# CRBN-60.net
KiCad netlist of a schematic drawn in EAGLE
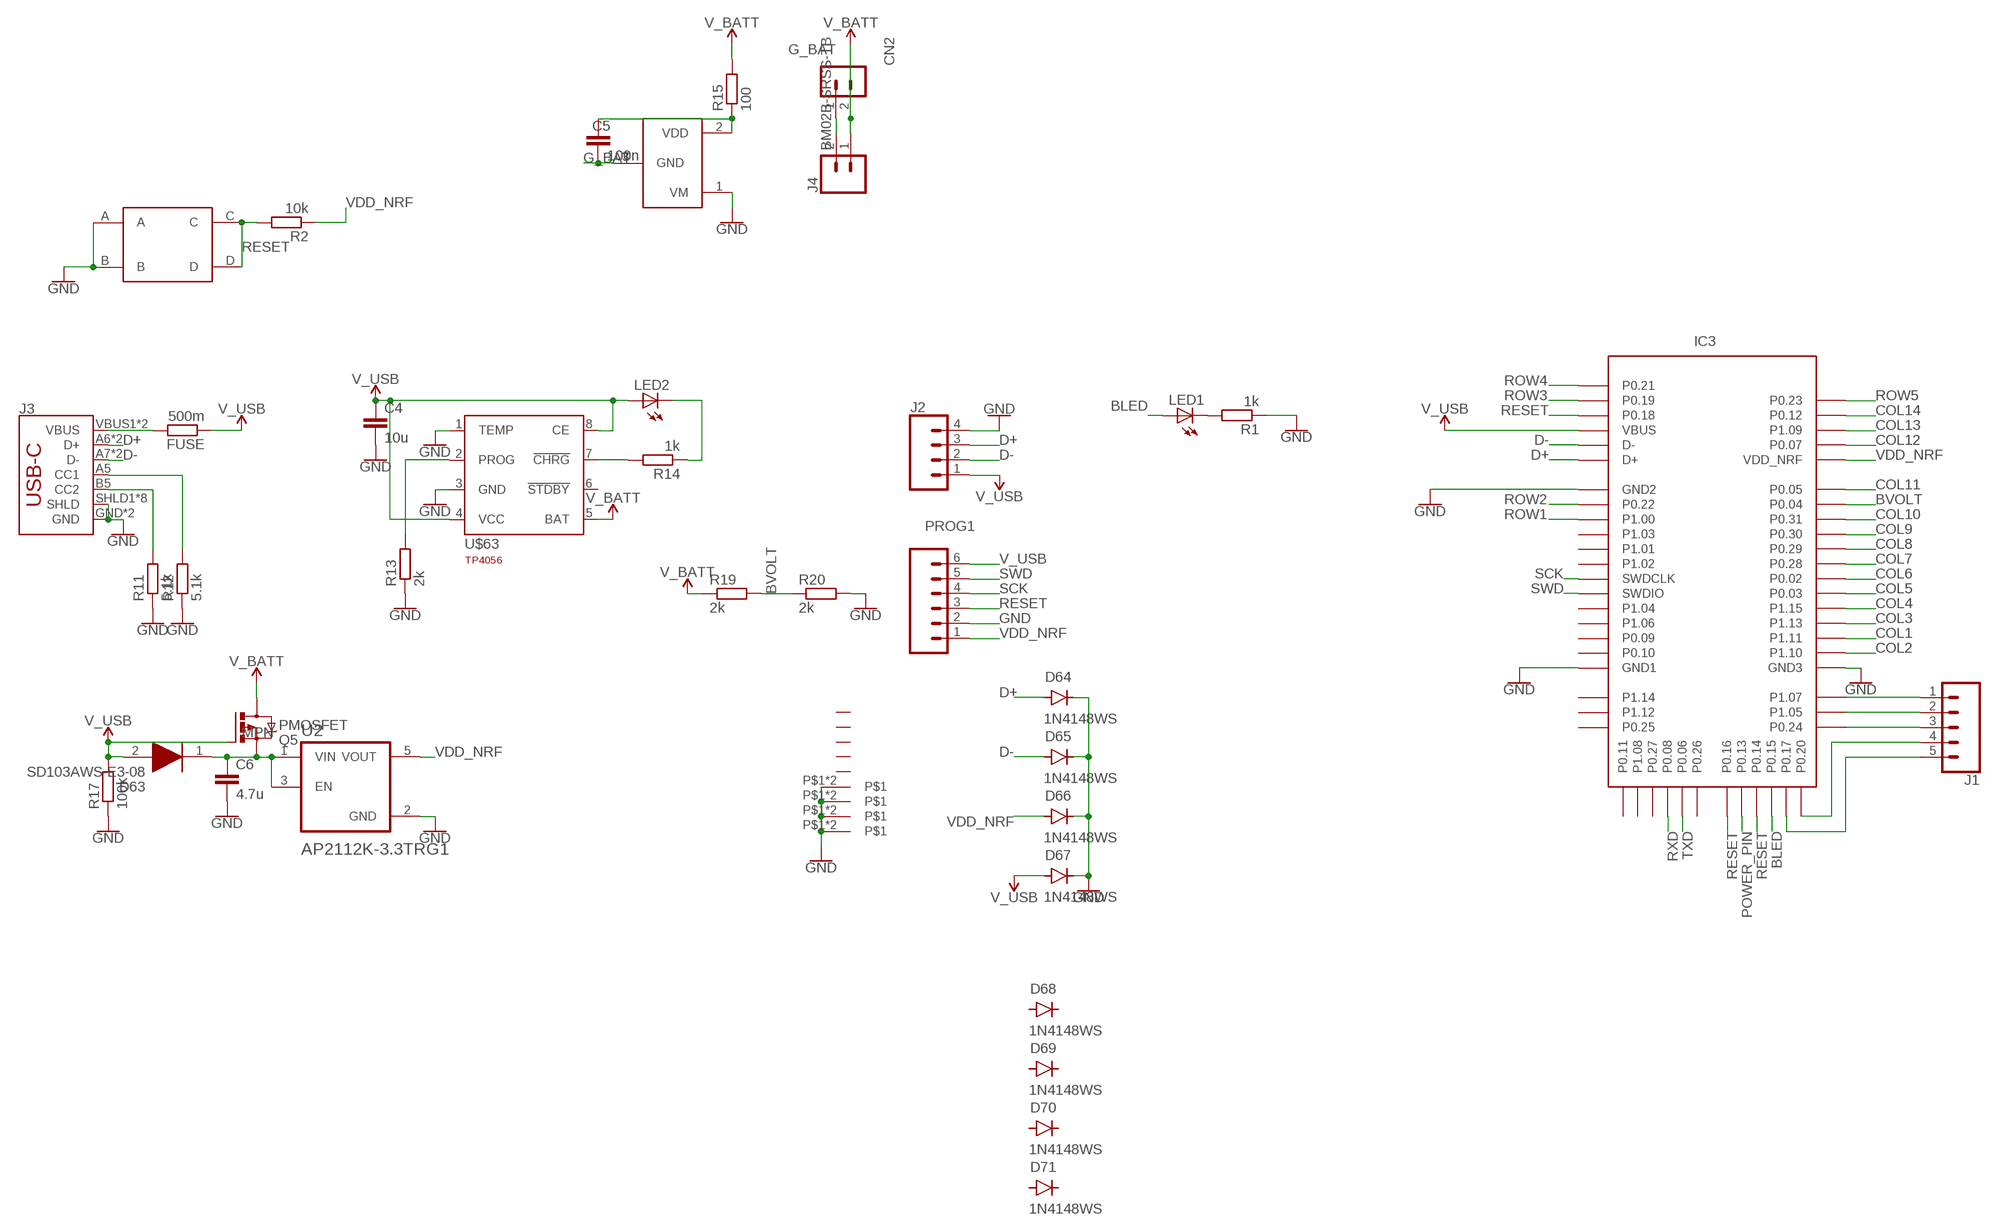
[diagram p0: schematic, sheet 1, part 1 of 2]
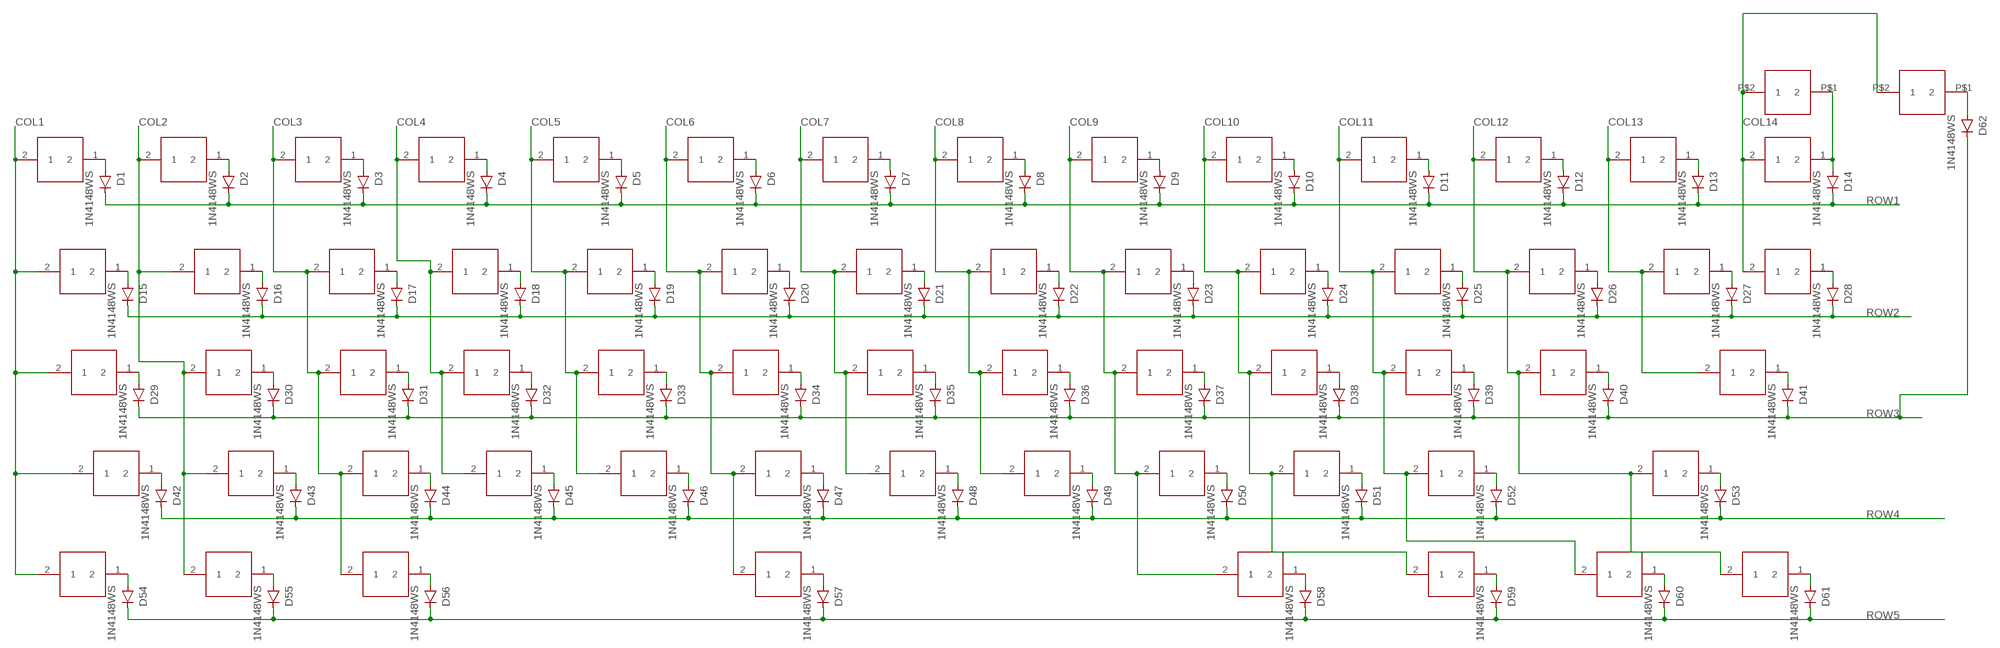
[diagram p1: schematic, sheet 1, part 2 of 2]

(export (version "E")
  (design (tool "Eeschema 10.0.6"))
  (components
    (comp (ref "C4")
      (value "10u")
      (footprint "eagle-import:C0603")
      (libsource (lib "eagle-import") (part "C-EUC0603"))
    )
    (comp (ref "C5")
      (value "100n")
      (footprint "eagle-import:C0603")
      (libsource (lib "eagle-import") (part "C-EUC0603"))
    )
    (comp (ref "C6")
      (value "4.7u")
      (footprint "eagle-import:C0603")
      (libsource (lib "eagle-import") (part "C-EUC0603"))
    )
    (comp (ref "CN2")
      (value "BM02B-SRSS-TB")
      (footprint "eagle-import:BM02B-SRSS-TB")
      (libsource (lib "eagle-import") (part "BM02B-SRSS-TB"))
    )
    (comp (ref "D1")
      (value "1N4148WS")
      (footprint "eagle-import:SOD-323")
      (fields
        (field (name "DIGIKEY_PART_NUMBER") "1N4148WSFSTR-ND")
        (field (name "MANUFACTURER") "Diodes Incorporated")
        (field (name "CREATED_BY") "PCBLayout.com")
      )
      (libsource (lib "eagle-import") (part "1N4148WS"))
    )
    (comp (ref "D2")
      (value "1N4148WS")
      (footprint "eagle-import:SOD-323")
      (fields
        (field (name "DIGIKEY_PART_NUMBER") "1N4148WSFSTR-ND")
        (field (name "MANUFACTURER") "Diodes Incorporated")
        (field (name "CREATED_BY") "PCBLayout.com")
      )
      (libsource (lib "eagle-import") (part "1N4148WS"))
    )
    (comp (ref "D3")
      (value "1N4148WS")
      (footprint "eagle-import:SOD-323")
      (fields
        (field (name "DIGIKEY_PART_NUMBER") "1N4148WSFSTR-ND")
        (field (name "MANUFACTURER") "Diodes Incorporated")
        (field (name "CREATED_BY") "PCBLayout.com")
      )
      (libsource (lib "eagle-import") (part "1N4148WS"))
    )
    (comp (ref "D4")
      (value "1N4148WS")
      (footprint "eagle-import:SOD-323")
      (fields
        (field (name "DIGIKEY_PART_NUMBER") "1N4148WSFSTR-ND")
        (field (name "MANUFACTURER") "Diodes Incorporated")
        (field (name "CREATED_BY") "PCBLayout.com")
      )
      (libsource (lib "eagle-import") (part "1N4148WS"))
    )
    (comp (ref "D5")
      (value "1N4148WS")
      (footprint "eagle-import:SOD-323")
      (fields
        (field (name "DIGIKEY_PART_NUMBER") "1N4148WSFSTR-ND")
        (field (name "MANUFACTURER") "Diodes Incorporated")
        (field (name "CREATED_BY") "PCBLayout.com")
      )
      (libsource (lib "eagle-import") (part "1N4148WS"))
    )
    (comp (ref "D6")
      (value "1N4148WS")
      (footprint "eagle-import:SOD-323")
      (fields
        (field (name "DIGIKEY_PART_NUMBER") "1N4148WSFSTR-ND")
        (field (name "MANUFACTURER") "Diodes Incorporated")
        (field (name "CREATED_BY") "PCBLayout.com")
      )
      (libsource (lib "eagle-import") (part "1N4148WS"))
    )
    (comp (ref "D7")
      (value "1N4148WS")
      (footprint "eagle-import:SOD-323")
      (fields
        (field (name "DIGIKEY_PART_NUMBER") "1N4148WSFSTR-ND")
        (field (name "MANUFACTURER") "Diodes Incorporated")
        (field (name "CREATED_BY") "PCBLayout.com")
      )
      (libsource (lib "eagle-import") (part "1N4148WS"))
    )
    (comp (ref "D8")
      (value "1N4148WS")
      (footprint "eagle-import:SOD-323")
      (fields
        (field (name "DIGIKEY_PART_NUMBER") "1N4148WSFSTR-ND")
        (field (name "MANUFACTURER") "Diodes Incorporated")
        (field (name "CREATED_BY") "PCBLayout.com")
      )
      (libsource (lib "eagle-import") (part "1N4148WS"))
    )
    (comp (ref "D9")
      (value "1N4148WS")
      (footprint "eagle-import:SOD-323")
      (fields
        (field (name "DIGIKEY_PART_NUMBER") "1N4148WSFSTR-ND")
        (field (name "MANUFACTURER") "Diodes Incorporated")
        (field (name "CREATED_BY") "PCBLayout.com")
      )
      (libsource (lib "eagle-import") (part "1N4148WS"))
    )
    (comp (ref "D10")
      (value "1N4148WS")
      (footprint "eagle-import:SOD-323")
      (fields
        (field (name "DIGIKEY_PART_NUMBER") "1N4148WSFSTR-ND")
        (field (name "MANUFACTURER") "Diodes Incorporated")
        (field (name "CREATED_BY") "PCBLayout.com")
      )
      (libsource (lib "eagle-import") (part "1N4148WS"))
    )
    (comp (ref "D11")
      (value "1N4148WS")
      (footprint "eagle-import:SOD-323")
      (fields
        (field (name "DIGIKEY_PART_NUMBER") "1N4148WSFSTR-ND")
        (field (name "MANUFACTURER") "Diodes Incorporated")
        (field (name "CREATED_BY") "PCBLayout.com")
      )
      (libsource (lib "eagle-import") (part "1N4148WS"))
    )
    (comp (ref "D12")
      (value "1N4148WS")
      (footprint "eagle-import:SOD-323")
      (fields
        (field (name "DIGIKEY_PART_NUMBER") "1N4148WSFSTR-ND")
        (field (name "MANUFACTURER") "Diodes Incorporated")
        (field (name "CREATED_BY") "PCBLayout.com")
      )
      (libsource (lib "eagle-import") (part "1N4148WS"))
    )
    (comp (ref "D13")
      (value "1N4148WS")
      (footprint "eagle-import:SOD-323")
      (fields
        (field (name "DIGIKEY_PART_NUMBER") "1N4148WSFSTR-ND")
        (field (name "MANUFACTURER") "Diodes Incorporated")
        (field (name "CREATED_BY") "PCBLayout.com")
      )
      (libsource (lib "eagle-import") (part "1N4148WS"))
    )
    (comp (ref "D14")
      (value "1N4148WS")
      (footprint "eagle-import:SOD-323")
      (fields
        (field (name "DIGIKEY_PART_NUMBER") "1N4148WSFSTR-ND")
        (field (name "MANUFACTURER") "Diodes Incorporated")
        (field (name "CREATED_BY") "PCBLayout.com")
      )
      (libsource (lib "eagle-import") (part "1N4148WS"))
    )
    (comp (ref "D15")
      (value "1N4148WS")
      (footprint "eagle-import:SOD-323")
      (fields
        (field (name "DIGIKEY_PART_NUMBER") "1N4148WSFSTR-ND")
        (field (name "MANUFACTURER") "Diodes Incorporated")
        (field (name "CREATED_BY") "PCBLayout.com")
      )
      (libsource (lib "eagle-import") (part "1N4148WS"))
    )
    (comp (ref "D16")
      (value "1N4148WS")
      (footprint "eagle-import:SOD-323")
      (fields
        (field (name "DIGIKEY_PART_NUMBER") "1N4148WSFSTR-ND")
        (field (name "MANUFACTURER") "Diodes Incorporated")
        (field (name "CREATED_BY") "PCBLayout.com")
      )
      (libsource (lib "eagle-import") (part "1N4148WS"))
    )
    (comp (ref "D17")
      (value "1N4148WS")
      (footprint "eagle-import:SOD-323")
      (fields
        (field (name "DIGIKEY_PART_NUMBER") "1N4148WSFSTR-ND")
        (field (name "MANUFACTURER") "Diodes Incorporated")
        (field (name "CREATED_BY") "PCBLayout.com")
      )
      (libsource (lib "eagle-import") (part "1N4148WS"))
    )
    (comp (ref "D18")
      (value "1N4148WS")
      (footprint "eagle-import:SOD-323")
      (fields
        (field (name "DIGIKEY_PART_NUMBER") "1N4148WSFSTR-ND")
        (field (name "MANUFACTURER") "Diodes Incorporated")
        (field (name "CREATED_BY") "PCBLayout.com")
      )
      (libsource (lib "eagle-import") (part "1N4148WS"))
    )
    (comp (ref "D19")
      (value "1N4148WS")
      (footprint "eagle-import:SOD-323")
      (fields
        (field (name "DIGIKEY_PART_NUMBER") "1N4148WSFSTR-ND")
        (field (name "MANUFACTURER") "Diodes Incorporated")
        (field (name "CREATED_BY") "PCBLayout.com")
      )
      (libsource (lib "eagle-import") (part "1N4148WS"))
    )
    (comp (ref "D20")
      (value "1N4148WS")
      (footprint "eagle-import:SOD-323")
      (fields
        (field (name "DIGIKEY_PART_NUMBER") "1N4148WSFSTR-ND")
        (field (name "MANUFACTURER") "Diodes Incorporated")
        (field (name "CREATED_BY") "PCBLayout.com")
      )
      (libsource (lib "eagle-import") (part "1N4148WS"))
    )
    (comp (ref "D21")
      (value "1N4148WS")
      (footprint "eagle-import:SOD-323")
      (fields
        (field (name "DIGIKEY_PART_NUMBER") "1N4148WSFSTR-ND")
        (field (name "MANUFACTURER") "Diodes Incorporated")
        (field (name "CREATED_BY") "PCBLayout.com")
      )
      (libsource (lib "eagle-import") (part "1N4148WS"))
    )
    (comp (ref "D22")
      (value "1N4148WS")
      (footprint "eagle-import:SOD-323")
      (fields
        (field (name "DIGIKEY_PART_NUMBER") "1N4148WSFSTR-ND")
        (field (name "MANUFACTURER") "Diodes Incorporated")
        (field (name "CREATED_BY") "PCBLayout.com")
      )
      (libsource (lib "eagle-import") (part "1N4148WS"))
    )
    (comp (ref "D23")
      (value "1N4148WS")
      (footprint "eagle-import:SOD-323")
      (fields
        (field (name "DIGIKEY_PART_NUMBER") "1N4148WSFSTR-ND")
        (field (name "MANUFACTURER") "Diodes Incorporated")
        (field (name "CREATED_BY") "PCBLayout.com")
      )
      (libsource (lib "eagle-import") (part "1N4148WS"))
    )
    (comp (ref "D24")
      (value "1N4148WS")
      (footprint "eagle-import:SOD-323")
      (fields
        (field (name "DIGIKEY_PART_NUMBER") "1N4148WSFSTR-ND")
        (field (name "MANUFACTURER") "Diodes Incorporated")
        (field (name "CREATED_BY") "PCBLayout.com")
      )
      (libsource (lib "eagle-import") (part "1N4148WS"))
    )
    (comp (ref "D25")
      (value "1N4148WS")
      (footprint "eagle-import:SOD-323")
      (fields
        (field (name "DIGIKEY_PART_NUMBER") "1N4148WSFSTR-ND")
        (field (name "MANUFACTURER") "Diodes Incorporated")
        (field (name "CREATED_BY") "PCBLayout.com")
      )
      (libsource (lib "eagle-import") (part "1N4148WS"))
    )
    (comp (ref "D26")
      (value "1N4148WS")
      (footprint "eagle-import:SOD-323")
      (fields
        (field (name "DIGIKEY_PART_NUMBER") "1N4148WSFSTR-ND")
        (field (name "MANUFACTURER") "Diodes Incorporated")
        (field (name "CREATED_BY") "PCBLayout.com")
      )
      (libsource (lib "eagle-import") (part "1N4148WS"))
    )
    (comp (ref "D27")
      (value "1N4148WS")
      (footprint "eagle-import:SOD-323")
      (fields
        (field (name "DIGIKEY_PART_NUMBER") "1N4148WSFSTR-ND")
        (field (name "MANUFACTURER") "Diodes Incorporated")
        (field (name "CREATED_BY") "PCBLayout.com")
      )
      (libsource (lib "eagle-import") (part "1N4148WS"))
    )
    (comp (ref "D28")
      (value "1N4148WS")
      (footprint "eagle-import:SOD-323")
      (fields
        (field (name "DIGIKEY_PART_NUMBER") "1N4148WSFSTR-ND")
        (field (name "MANUFACTURER") "Diodes Incorporated")
        (field (name "CREATED_BY") "PCBLayout.com")
      )
      (libsource (lib "eagle-import") (part "1N4148WS"))
    )
    (comp (ref "D29")
      (value "1N4148WS")
      (footprint "eagle-import:SOD-323")
      (fields
        (field (name "DIGIKEY_PART_NUMBER") "1N4148WSFSTR-ND")
        (field (name "MANUFACTURER") "Diodes Incorporated")
        (field (name "CREATED_BY") "PCBLayout.com")
      )
      (libsource (lib "eagle-import") (part "1N4148WS"))
    )
    (comp (ref "D30")
      (value "1N4148WS")
      (footprint "eagle-import:SOD-323")
      (fields
        (field (name "DIGIKEY_PART_NUMBER") "1N4148WSFSTR-ND")
        (field (name "MANUFACTURER") "Diodes Incorporated")
        (field (name "CREATED_BY") "PCBLayout.com")
      )
      (libsource (lib "eagle-import") (part "1N4148WS"))
    )
    (comp (ref "D31")
      (value "1N4148WS")
      (footprint "eagle-import:SOD-323")
      (fields
        (field (name "DIGIKEY_PART_NUMBER") "1N4148WSFSTR-ND")
        (field (name "MANUFACTURER") "Diodes Incorporated")
        (field (name "CREATED_BY") "PCBLayout.com")
      )
      (libsource (lib "eagle-import") (part "1N4148WS"))
    )
    (comp (ref "D32")
      (value "1N4148WS")
      (footprint "eagle-import:SOD-323")
      (fields
        (field (name "DIGIKEY_PART_NUMBER") "1N4148WSFSTR-ND")
        (field (name "MANUFACTURER") "Diodes Incorporated")
        (field (name "CREATED_BY") "PCBLayout.com")
      )
      (libsource (lib "eagle-import") (part "1N4148WS"))
    )
    (comp (ref "D33")
      (value "1N4148WS")
      (footprint "eagle-import:SOD-323")
      (fields
        (field (name "DIGIKEY_PART_NUMBER") "1N4148WSFSTR-ND")
        (field (name "MANUFACTURER") "Diodes Incorporated")
        (field (name "CREATED_BY") "PCBLayout.com")
      )
      (libsource (lib "eagle-import") (part "1N4148WS"))
    )
    (comp (ref "D34")
      (value "1N4148WS")
      (footprint "eagle-import:SOD-323")
      (fields
        (field (name "DIGIKEY_PART_NUMBER") "1N4148WSFSTR-ND")
        (field (name "MANUFACTURER") "Diodes Incorporated")
        (field (name "CREATED_BY") "PCBLayout.com")
      )
      (libsource (lib "eagle-import") (part "1N4148WS"))
    )
    (comp (ref "D35")
      (value "1N4148WS")
      (footprint "eagle-import:SOD-323")
      (fields
        (field (name "DIGIKEY_PART_NUMBER") "1N4148WSFSTR-ND")
        (field (name "MANUFACTURER") "Diodes Incorporated")
        (field (name "CREATED_BY") "PCBLayout.com")
      )
      (libsource (lib "eagle-import") (part "1N4148WS"))
    )
    (comp (ref "D36")
      (value "1N4148WS")
      (footprint "eagle-import:SOD-323")
      (fields
        (field (name "DIGIKEY_PART_NUMBER") "1N4148WSFSTR-ND")
        (field (name "MANUFACTURER") "Diodes Incorporated")
        (field (name "CREATED_BY") "PCBLayout.com")
      )
      (libsource (lib "eagle-import") (part "1N4148WS"))
    )
    (comp (ref "D37")
      (value "1N4148WS")
      (footprint "eagle-import:SOD-323")
      (fields
        (field (name "DIGIKEY_PART_NUMBER") "1N4148WSFSTR-ND")
        (field (name "MANUFACTURER") "Diodes Incorporated")
        (field (name "CREATED_BY") "PCBLayout.com")
      )
      (libsource (lib "eagle-import") (part "1N4148WS"))
    )
    (comp (ref "D38")
      (value "1N4148WS")
      (footprint "eagle-import:SOD-323")
      (fields
        (field (name "DIGIKEY_PART_NUMBER") "1N4148WSFSTR-ND")
        (field (name "MANUFACTURER") "Diodes Incorporated")
        (field (name "CREATED_BY") "PCBLayout.com")
      )
      (libsource (lib "eagle-import") (part "1N4148WS"))
    )
    (comp (ref "D39")
      (value "1N4148WS")
      (footprint "eagle-import:SOD-323")
      (fields
        (field (name "DIGIKEY_PART_NUMBER") "1N4148WSFSTR-ND")
        (field (name "MANUFACTURER") "Diodes Incorporated")
        (field (name "CREATED_BY") "PCBLayout.com")
      )
      (libsource (lib "eagle-import") (part "1N4148WS"))
    )
    (comp (ref "D40")
      (value "1N4148WS")
      (footprint "eagle-import:SOD-323")
      (fields
        (field (name "DIGIKEY_PART_NUMBER") "1N4148WSFSTR-ND")
        (field (name "MANUFACTURER") "Diodes Incorporated")
        (field (name "CREATED_BY") "PCBLayout.com")
      )
      (libsource (lib "eagle-import") (part "1N4148WS"))
    )
    (comp (ref "D41")
      (value "1N4148WS")
      (footprint "eagle-import:SOD-323")
      (fields
        (field (name "DIGIKEY_PART_NUMBER") "1N4148WSFSTR-ND")
        (field (name "MANUFACTURER") "Diodes Incorporated")
        (field (name "CREATED_BY") "PCBLayout.com")
      )
      (libsource (lib "eagle-import") (part "1N4148WS"))
    )
    (comp (ref "D42")
      (value "1N4148WS")
      (footprint "eagle-import:SOD-323")
      (fields
        (field (name "DIGIKEY_PART_NUMBER") "1N4148WSFSTR-ND")
        (field (name "MANUFACTURER") "Diodes Incorporated")
        (field (name "CREATED_BY") "PCBLayout.com")
      )
      (libsource (lib "eagle-import") (part "1N4148WS"))
    )
    (comp (ref "D43")
      (value "1N4148WS")
      (footprint "eagle-import:SOD-323")
      (fields
        (field (name "DIGIKEY_PART_NUMBER") "1N4148WSFSTR-ND")
        (field (name "MANUFACTURER") "Diodes Incorporated")
        (field (name "CREATED_BY") "PCBLayout.com")
      )
      (libsource (lib "eagle-import") (part "1N4148WS"))
    )
    (comp (ref "D44")
      (value "1N4148WS")
      (footprint "eagle-import:SOD-323")
      (fields
        (field (name "DIGIKEY_PART_NUMBER") "1N4148WSFSTR-ND")
        (field (name "MANUFACTURER") "Diodes Incorporated")
        (field (name "CREATED_BY") "PCBLayout.com")
      )
      (libsource (lib "eagle-import") (part "1N4148WS"))
    )
    (comp (ref "D45")
      (value "1N4148WS")
      (footprint "eagle-import:SOD-323")
      (fields
        (field (name "DIGIKEY_PART_NUMBER") "1N4148WSFSTR-ND")
        (field (name "MANUFACTURER") "Diodes Incorporated")
        (field (name "CREATED_BY") "PCBLayout.com")
      )
      (libsource (lib "eagle-import") (part "1N4148WS"))
    )
    (comp (ref "D46")
      (value "1N4148WS")
      (footprint "eagle-import:SOD-323")
      (fields
        (field (name "DIGIKEY_PART_NUMBER") "1N4148WSFSTR-ND")
        (field (name "MANUFACTURER") "Diodes Incorporated")
        (field (name "CREATED_BY") "PCBLayout.com")
      )
      (libsource (lib "eagle-import") (part "1N4148WS"))
    )
    (comp (ref "D47")
      (value "1N4148WS")
      (footprint "eagle-import:SOD-323")
      (fields
        (field (name "DIGIKEY_PART_NUMBER") "1N4148WSFSTR-ND")
        (field (name "MANUFACTURER") "Diodes Incorporated")
        (field (name "CREATED_BY") "PCBLayout.com")
      )
      (libsource (lib "eagle-import") (part "1N4148WS"))
    )
    (comp (ref "D48")
      (value "1N4148WS")
      (footprint "eagle-import:SOD-323")
      (fields
        (field (name "DIGIKEY_PART_NUMBER") "1N4148WSFSTR-ND")
        (field (name "MANUFACTURER") "Diodes Incorporated")
        (field (name "CREATED_BY") "PCBLayout.com")
      )
      (libsource (lib "eagle-import") (part "1N4148WS"))
    )
    (comp (ref "D49")
      (value "1N4148WS")
      (footprint "eagle-import:SOD-323")
      (fields
        (field (name "DIGIKEY_PART_NUMBER") "1N4148WSFSTR-ND")
        (field (name "MANUFACTURER") "Diodes Incorporated")
        (field (name "CREATED_BY") "PCBLayout.com")
      )
      (libsource (lib "eagle-import") (part "1N4148WS"))
    )
    (comp (ref "D50")
      (value "1N4148WS")
      (footprint "eagle-import:SOD-323")
      (fields
        (field (name "DIGIKEY_PART_NUMBER") "1N4148WSFSTR-ND")
        (field (name "MANUFACTURER") "Diodes Incorporated")
        (field (name "CREATED_BY") "PCBLayout.com")
      )
      (libsource (lib "eagle-import") (part "1N4148WS"))
    )
    (comp (ref "D51")
      (value "1N4148WS")
      (footprint "eagle-import:SOD-323")
      (fields
        (field (name "DIGIKEY_PART_NUMBER") "1N4148WSFSTR-ND")
        (field (name "MANUFACTURER") "Diodes Incorporated")
        (field (name "CREATED_BY") "PCBLayout.com")
      )
      (libsource (lib "eagle-import") (part "1N4148WS"))
    )
    (comp (ref "D52")
      (value "1N4148WS")
      (footprint "eagle-import:SOD-323")
      (fields
        (field (name "DIGIKEY_PART_NUMBER") "1N4148WSFSTR-ND")
        (field (name "MANUFACTURER") "Diodes Incorporated")
        (field (name "CREATED_BY") "PCBLayout.com")
      )
      (libsource (lib "eagle-import") (part "1N4148WS"))
    )
    (comp (ref "D53")
      (value "1N4148WS")
      (footprint "eagle-import:SOD-323")
      (fields
        (field (name "DIGIKEY_PART_NUMBER") "1N4148WSFSTR-ND")
        (field (name "MANUFACTURER") "Diodes Incorporated")
        (field (name "CREATED_BY") "PCBLayout.com")
      )
      (libsource (lib "eagle-import") (part "1N4148WS"))
    )
    (comp (ref "D54")
      (value "1N4148WS")
      (footprint "eagle-import:SOD-323")
      (fields
        (field (name "DIGIKEY_PART_NUMBER") "1N4148WSFSTR-ND")
        (field (name "MANUFACTURER") "Diodes Incorporated")
        (field (name "CREATED_BY") "PCBLayout.com")
      )
      (libsource (lib "eagle-import") (part "1N4148WS"))
    )
    (comp (ref "D55")
      (value "1N4148WS")
      (footprint "eagle-import:SOD-323")
      (fields
        (field (name "DIGIKEY_PART_NUMBER") "1N4148WSFSTR-ND")
        (field (name "MANUFACTURER") "Diodes Incorporated")
        (field (name "CREATED_BY") "PCBLayout.com")
      )
      (libsource (lib "eagle-import") (part "1N4148WS"))
    )
    (comp (ref "D56")
      (value "1N4148WS")
      (footprint "eagle-import:SOD-323")
      (fields
        (field (name "DIGIKEY_PART_NUMBER") "1N4148WSFSTR-ND")
        (field (name "MANUFACTURER") "Diodes Incorporated")
        (field (name "CREATED_BY") "PCBLayout.com")
      )
      (libsource (lib "eagle-import") (part "1N4148WS"))
    )
    (comp (ref "D57")
      (value "1N4148WS")
      (footprint "eagle-import:SOD-323")
      (fields
        (field (name "DIGIKEY_PART_NUMBER") "1N4148WSFSTR-ND")
        (field (name "MANUFACTURER") "Diodes Incorporated")
        (field (name "CREATED_BY") "PCBLayout.com")
      )
      (libsource (lib "eagle-import") (part "1N4148WS"))
    )
    (comp (ref "D58")
      (value "1N4148WS")
      (footprint "eagle-import:SOD-323")
      (fields
        (field (name "DIGIKEY_PART_NUMBER") "1N4148WSFSTR-ND")
        (field (name "MANUFACTURER") "Diodes Incorporated")
        (field (name "CREATED_BY") "PCBLayout.com")
      )
      (libsource (lib "eagle-import") (part "1N4148WS"))
    )
    (comp (ref "D59")
      (value "1N4148WS")
      (footprint "eagle-import:SOD-323")
      (fields
        (field (name "DIGIKEY_PART_NUMBER") "1N4148WSFSTR-ND")
        (field (name "MANUFACTURER") "Diodes Incorporated")
        (field (name "CREATED_BY") "PCBLayout.com")
      )
      (libsource (lib "eagle-import") (part "1N4148WS"))
    )
    (comp (ref "D60")
      (value "1N4148WS")
      (footprint "eagle-import:SOD-323")
      (fields
        (field (name "DIGIKEY_PART_NUMBER") "1N4148WSFSTR-ND")
        (field (name "MANUFACTURER") "Diodes Incorporated")
        (field (name "CREATED_BY") "PCBLayout.com")
      )
      (libsource (lib "eagle-import") (part "1N4148WS"))
    )
    (comp (ref "D61")
      (value "1N4148WS")
      (footprint "eagle-import:SOD-323")
      (fields
        (field (name "DIGIKEY_PART_NUMBER") "1N4148WSFSTR-ND")
        (field (name "MANUFACTURER") "Diodes Incorporated")
        (field (name "CREATED_BY") "PCBLayout.com")
      )
      (libsource (lib "eagle-import") (part "1N4148WS"))
    )
    (comp (ref "D62")
      (value "1N4148WS")
      (footprint "eagle-import:SOD-323")
      (fields
        (field (name "DIGIKEY_PART_NUMBER") "1N4148WSFSTR-ND")
        (field (name "MANUFACTURER") "Diodes Incorporated")
        (field (name "CREATED_BY") "PCBLayout.com")
      )
      (libsource (lib "eagle-import") (part "1N4148WS"))
    )
    (comp (ref "D63")
      (value "SD103AWS-E3-08")
      (footprint "eagle-import:SOD2713X115N")
      (fields (field (name "MOUSER_PART_NUMBER") "78-SD103AWS-E3-08"))
      (libsource (lib "eagle-import") (part "SD103AWS-E3-08"))
    )
    (comp (ref "D64")
      (value "1N4148WS")
      (footprint "eagle-import:SOD-323")
      (fields
        (field (name "DIGIKEY_PART_NUMBER") "1N4148WSFSTR-ND")
        (field (name "MANUFACTURER") "Diodes Incorporated")
        (field (name "CREATED_BY") "PCBLayout.com")
      )
      (libsource (lib "eagle-import") (part "1N4148WS"))
    )
    (comp (ref "D65")
      (value "1N4148WS")
      (footprint "eagle-import:SOD-323")
      (fields
        (field (name "DIGIKEY_PART_NUMBER") "1N4148WSFSTR-ND")
        (field (name "MANUFACTURER") "Diodes Incorporated")
        (field (name "CREATED_BY") "PCBLayout.com")
      )
      (libsource (lib "eagle-import") (part "1N4148WS"))
    )
    (comp (ref "D66")
      (value "1N4148WS")
      (footprint "eagle-import:SOD-323")
      (fields
        (field (name "DIGIKEY_PART_NUMBER") "1N4148WSFSTR-ND")
        (field (name "MANUFACTURER") "Diodes Incorporated")
        (field (name "CREATED_BY") "PCBLayout.com")
      )
      (libsource (lib "eagle-import") (part "1N4148WS"))
    )
    (comp (ref "D67")
      (value "1N4148WS")
      (footprint "eagle-import:SOD-323")
      (fields
        (field (name "DIGIKEY_PART_NUMBER") "1N4148WSFSTR-ND")
        (field (name "MANUFACTURER") "Diodes Incorporated")
        (field (name "CREATED_BY") "PCBLayout.com")
      )
      (libsource (lib "eagle-import") (part "1N4148WS"))
    )
    (comp (ref "D68")
      (value "1N4148WS")
      (footprint "eagle-import:SOD-323")
      (fields
        (field (name "DIGIKEY_PART_NUMBER") "1N4148WSFSTR-ND")
        (field (name "MANUFACTURER") "Diodes Incorporated")
        (field (name "CREATED_BY") "PCBLayout.com")
      )
      (libsource (lib "eagle-import") (part "1N4148WS"))
    )
    (comp (ref "D69")
      (value "1N4148WS")
      (footprint "eagle-import:SOD-323")
      (fields
        (field (name "DIGIKEY_PART_NUMBER") "1N4148WSFSTR-ND")
        (field (name "MANUFACTURER") "Diodes Incorporated")
        (field (name "CREATED_BY") "PCBLayout.com")
      )
      (libsource (lib "eagle-import") (part "1N4148WS"))
    )
    (comp (ref "D70")
      (value "1N4148WS")
      (footprint "eagle-import:SOD-323")
      (fields
        (field (name "DIGIKEY_PART_NUMBER") "1N4148WSFSTR-ND")
        (field (name "MANUFACTURER") "Diodes Incorporated")
        (field (name "CREATED_BY") "PCBLayout.com")
      )
      (libsource (lib "eagle-import") (part "1N4148WS"))
    )
    (comp (ref "D71")
      (value "1N4148WS")
      (footprint "eagle-import:SOD-323")
      (fields
        (field (name "DIGIKEY_PART_NUMBER") "1N4148WSFSTR-ND")
        (field (name "MANUFACTURER") "Diodes Incorporated")
        (field (name "CREATED_BY") "PCBLayout.com")
      )
      (libsource (lib "eagle-import") (part "1N4148WS"))
    )
    (comp (ref "FUSE")
      (value "500m")
      (footprint "eagle-import:R0603")
      (libsource (lib "eagle-import") (part "R-EU_R0603"))
    )
    (comp (ref "IC1")
      (value "XB3303ASOT23")
      (footprint "eagle-import:SOT23-3")
      (libsource (lib "eagle-import") (part "XB3303ASOT23"))
    )
    (comp (ref "IC3")
      (value "HOLYIOT_18010")
      (footprint "eagle-import:PCBCOMPONENT_1")
      (libsource (lib "eagle-import") (part "HOLYIOT_18010"))
    )
    (comp (ref "J1")
      (value "CONN_051.27MM")
      (footprint "eagle-import:1X05_1.27MM")
      (libsource (lib "eagle-import") (part "CONN_051.27MM"))
    )
    (comp (ref "J2")
      (value "CONN_041X04_NO_SILK")
      (footprint "eagle-import:1X04_NO_SILK")
      (libsource (lib "eagle-import") (part "CONN_041X04_NO_SILK"))
    )
    (comp (ref "J3")
      (value "SPARKFUN-CONNECTORS_USB_C16PIN")
      (footprint "eagle-import:SPARKFUN-CONNECTORS_USB-C-16P")
      (libsource (lib "eagle-import") (part "SPARKFUN-CONNECTORS_USB_C16PIN"))
    )
    (comp (ref "J4")
      (value "CONN_02")
      (footprint "eagle-import:1X02")
      (libsource (lib "eagle-import") (part "CONN_02"))
    )
    (comp (ref "LED1")
      (value "LEDCHIPLED_0805")
      (footprint "eagle-import:CHIPLED_0805")
      (libsource (lib "eagle-import") (part "LEDCHIPLED_0805"))
    )
    (comp (ref "LED2")
      (value "LEDCHIPLED_0805")
      (footprint "eagle-import:CHIPLED_0805")
      (libsource (lib "eagle-import") (part "LEDCHIPLED_0805"))
    )
    (comp (ref "PROG1")
      (value "CONN_06NO_SILK_FEMALE_PTH")
      (footprint "eagle-import:1X06_NO_SILK")
      (libsource (lib "eagle-import") (part "CONN_06NO_SILK_FEMALE_PTH"))
    )
    (comp (ref "Q5")
      (value "PMOSFET")
      (footprint "eagle-import:SOT23")
      (fields (field (name "MPN") "SL2301S"))
      (libsource (lib "eagle-import") (part "PMOSFETSOT23_"))
    )
    (comp (ref "R1")
      (value "1k")
      (footprint "eagle-import:R0603")
      (libsource (lib "eagle-import") (part "R-EU_R0603"))
    )
    (comp (ref "R2")
      (value "10k")
      (footprint "eagle-import:R0603")
      (libsource (lib "eagle-import") (part "R-EU_R0603"))
    )
    (comp (ref "R11")
      (value "5.1k")
      (footprint "eagle-import:R0603")
      (libsource (lib "eagle-import") (part "R-EU_R0603"))
    )
    (comp (ref "R12")
      (value "5.1k")
      (footprint "eagle-import:R0603")
      (libsource (lib "eagle-import") (part "R-EU_R0603"))
    )
    (comp (ref "R13")
      (value "2k")
      (footprint "eagle-import:R0603")
      (libsource (lib "eagle-import") (part "R-EU_R0603"))
    )
    (comp (ref "R14")
      (value "1k")
      (footprint "eagle-import:R0603")
      (libsource (lib "eagle-import") (part "R-EU_R0603"))
    )
    (comp (ref "R15")
      (value "100")
      (footprint "eagle-import:R0603")
      (libsource (lib "eagle-import") (part "R-EU_R0603"))
    )
    (comp (ref "R17")
      (value "100k")
      (footprint "eagle-import:R0603")
      (libsource (lib "eagle-import") (part "R-EU_R0603"))
    )
    (comp (ref "R19")
      (value "2k")
      (footprint "eagle-import:R0603")
      (libsource (lib "eagle-import") (part "R-EU_R0603"))
    )
    (comp (ref "R20")
      (value "2k")
      (footprint "eagle-import:R0603")
      (libsource (lib "eagle-import") (part "R-EU_R0603"))
    )
    (comp (ref "U$1")
      (value "CHERRY")
      (footprint "eagle-import:CHERRY")
      (libsource (lib "eagle-import") (part "CHERRY"))
    )
    (comp (ref "U$2")
      (value "CHERRY")
      (footprint "eagle-import:CHERRY")
      (libsource (lib "eagle-import") (part "CHERRY"))
    )
    (comp (ref "U$3")
      (value "CHERRY")
      (footprint "eagle-import:CHERRY")
      (libsource (lib "eagle-import") (part "CHERRY"))
    )
    (comp (ref "U$4")
      (value "CHERRY")
      (footprint "eagle-import:CHERRY")
      (libsource (lib "eagle-import") (part "CHERRY"))
    )
    (comp (ref "U$5")
      (value "CHERRY")
      (footprint "eagle-import:CHERRY")
      (libsource (lib "eagle-import") (part "CHERRY"))
    )
    (comp (ref "U$6")
      (value "CHERRY")
      (footprint "eagle-import:CHERRY")
      (libsource (lib "eagle-import") (part "CHERRY"))
    )
    (comp (ref "U$7")
      (value "CHERRY")
      (footprint "eagle-import:CHERRY")
      (libsource (lib "eagle-import") (part "CHERRY"))
    )
    (comp (ref "U$8")
      (value "CHERRY")
      (footprint "eagle-import:CHERRY")
      (libsource (lib "eagle-import") (part "CHERRY"))
    )
    (comp (ref "U$9")
      (value "CHERRY")
      (footprint "eagle-import:CHERRY")
      (libsource (lib "eagle-import") (part "CHERRY"))
    )
    (comp (ref "U$10")
      (value "CHERRY")
      (footprint "eagle-import:CHERRY")
      (libsource (lib "eagle-import") (part "CHERRY"))
    )
    (comp (ref "U$11")
      (value "CHERRY")
      (footprint "eagle-import:CHERRY")
      (libsource (lib "eagle-import") (part "CHERRY"))
    )
    (comp (ref "U$12")
      (value "CHERRY")
      (footprint "eagle-import:CHERRY")
      (libsource (lib "eagle-import") (part "CHERRY"))
    )
    (comp (ref "U$13")
      (value "CHERRY")
      (footprint "eagle-import:CHERRY")
      (libsource (lib "eagle-import") (part "CHERRY"))
    )
    (comp (ref "U$14")
      (value "CHERRY_CORNER_OFFED")
      (footprint "eagle-import:CHERRY_CORNER_OFFED")
      (libsource (lib "eagle-import") (part "CHERRY_CORNER_OFFED"))
    )
    (comp (ref "U$15")
      (value "CHERRY")
      (footprint "eagle-import:CHERRY")
      (libsource (lib "eagle-import") (part "CHERRY"))
    )
    (comp (ref "U$16")
      (value "CHERRY")
      (footprint "eagle-import:CHERRY")
      (libsource (lib "eagle-import") (part "CHERRY"))
    )
    (comp (ref "U$17")
      (value "CHERRY")
      (footprint "eagle-import:CHERRY")
      (libsource (lib "eagle-import") (part "CHERRY"))
    )
    (comp (ref "U$18")
      (value "CHERRY")
      (footprint "eagle-import:CHERRY")
      (libsource (lib "eagle-import") (part "CHERRY"))
    )
    (comp (ref "U$19")
      (value "CHERRY")
      (footprint "eagle-import:CHERRY")
      (libsource (lib "eagle-import") (part "CHERRY"))
    )
    (comp (ref "U$20")
      (value "CHERRY")
      (footprint "eagle-import:CHERRY")
      (libsource (lib "eagle-import") (part "CHERRY"))
    )
    (comp (ref "U$21")
      (value "CHERRY")
      (footprint "eagle-import:CHERRY")
      (libsource (lib "eagle-import") (part "CHERRY"))
    )
    (comp (ref "U$22")
      (value "CHERRY")
      (footprint "eagle-import:CHERRY")
      (libsource (lib "eagle-import") (part "CHERRY"))
    )
    (comp (ref "U$23")
      (value "CHERRY")
      (footprint "eagle-import:CHERRY")
      (libsource (lib "eagle-import") (part "CHERRY"))
    )
    (comp (ref "U$24")
      (value "CHERRY")
      (footprint "eagle-import:CHERRY")
      (libsource (lib "eagle-import") (part "CHERRY"))
    )
    (comp (ref "U$25")
      (value "CHERRY")
      (footprint "eagle-import:CHERRY")
      (libsource (lib "eagle-import") (part "CHERRY"))
    )
    (comp (ref "U$26")
      (value "CHERRY")
      (footprint "eagle-import:CHERRY")
      (libsource (lib "eagle-import") (part "CHERRY"))
    )
    (comp (ref "U$27")
      (value "CHERRY")
      (footprint "eagle-import:CHERRY")
      (libsource (lib "eagle-import") (part "CHERRY"))
    )
    (comp (ref "U$28")
      (value "CHERRY_CORNER_OFFED")
      (footprint "eagle-import:CHERRY_CORNER_OFFED")
      (libsource (lib "eagle-import") (part "CHERRY_CORNER_OFFED"))
    )
    (comp (ref "U$29")
      (value "CHERRY")
      (footprint "eagle-import:CHERRY")
      (libsource (lib "eagle-import") (part "CHERRY"))
    )
    (comp (ref "U$30")
      (value "CHERRY")
      (footprint "eagle-import:CHERRY")
      (libsource (lib "eagle-import") (part "CHERRY"))
    )
    (comp (ref "U$31")
      (value "CHERRY")
      (footprint "eagle-import:CHERRY")
      (libsource (lib "eagle-import") (part "CHERRY"))
    )
    (comp (ref "U$32")
      (value "CHERRY")
      (footprint "eagle-import:CHERRY")
      (libsource (lib "eagle-import") (part "CHERRY"))
    )
    (comp (ref "U$33")
      (value "CHERRY")
      (footprint "eagle-import:CHERRY")
      (libsource (lib "eagle-import") (part "CHERRY"))
    )
    (comp (ref "U$34")
      (value "CHERRY")
      (footprint "eagle-import:CHERRY")
      (libsource (lib "eagle-import") (part "CHERRY"))
    )
    (comp (ref "U$35")
      (value "CHERRY_CORNER_OFFED")
      (footprint "eagle-import:CHERRY_CORNER_OFFED")
      (libsource (lib "eagle-import") (part "CHERRY_CORNER_OFFED"))
    )
    (comp (ref "U$36")
      (value "CHERRY")
      (footprint "eagle-import:CHERRY")
      (libsource (lib "eagle-import") (part "CHERRY"))
    )
    (comp (ref "U$37")
      (value "CHERRY")
      (footprint "eagle-import:CHERRY")
      (libsource (lib "eagle-import") (part "CHERRY"))
    )
    (comp (ref "U$38")
      (value "CHERRY")
      (footprint "eagle-import:CHERRY")
      (libsource (lib "eagle-import") (part "CHERRY"))
    )
    (comp (ref "U$39")
      (value "CHERRY")
      (footprint "eagle-import:CHERRY")
      (libsource (lib "eagle-import") (part "CHERRY"))
    )
    (comp (ref "U$40")
      (value "CHERRY")
      (footprint "eagle-import:CHERRY")
      (libsource (lib "eagle-import") (part "CHERRY"))
    )
    (comp (ref "U$41")
      (value "CHERRY")
      (footprint "eagle-import:CHERRY")
      (libsource (lib "eagle-import") (part "CHERRY"))
    )
    (comp (ref "U$42")
      (value "CHERRY")
      (footprint "eagle-import:CHERRY")
      (libsource (lib "eagle-import") (part "CHERRY"))
    )
    (comp (ref "U$43")
      (value "CHERRY")
      (footprint "eagle-import:CHERRY")
      (libsource (lib "eagle-import") (part "CHERRY"))
    )
    (comp (ref "U$44")
      (value "CHERRY")
      (footprint "eagle-import:CHERRY")
      (libsource (lib "eagle-import") (part "CHERRY"))
    )
    (comp (ref "U$45")
      (value "CHERRY")
      (footprint "eagle-import:CHERRY")
      (libsource (lib "eagle-import") (part "CHERRY"))
    )
    (comp (ref "U$46")
      (value "CHERRY")
      (footprint "eagle-import:CHERRY")
      (libsource (lib "eagle-import") (part "CHERRY"))
    )
    (comp (ref "U$47")
      (value "CHERRY")
      (footprint "eagle-import:CHERRY")
      (libsource (lib "eagle-import") (part "CHERRY"))
    )
    (comp (ref "U$48")
      (value "CHERRY")
      (footprint "eagle-import:CHERRY")
      (libsource (lib "eagle-import") (part "CHERRY"))
    )
    (comp (ref "U$49")
      (value "CHERRY")
      (footprint "eagle-import:CHERRY")
      (libsource (lib "eagle-import") (part "CHERRY"))
    )
    (comp (ref "U$50")
      (value "CHERRY")
      (footprint "eagle-import:CHERRY")
      (libsource (lib "eagle-import") (part "CHERRY"))
    )
    (comp (ref "U$51")
      (value "CHERRY")
      (footprint "eagle-import:CHERRY")
      (libsource (lib "eagle-import") (part "CHERRY"))
    )
    (comp (ref "U$52")
      (value "CHERRY")
      (footprint "eagle-import:CHERRY")
      (libsource (lib "eagle-import") (part "CHERRY"))
    )
    (comp (ref "U$53")
      (value "CHERRY")
      (footprint "eagle-import:CHERRY")
      (libsource (lib "eagle-import") (part "CHERRY"))
    )
    (comp (ref "U$54")
      (value "CHERRY")
      (footprint "eagle-import:CHERRY")
      (libsource (lib "eagle-import") (part "CHERRY"))
    )
    (comp (ref "U$55")
      (value "CHERRY")
      (footprint "eagle-import:CHERRY")
      (libsource (lib "eagle-import") (part "CHERRY"))
    )
    (comp (ref "U$56")
      (value "CHERRY")
      (footprint "eagle-import:CHERRY")
      (libsource (lib "eagle-import") (part "CHERRY"))
    )
    (comp (ref "U$57")
      (value "CHERRY")
      (footprint "eagle-import:CHERRY")
      (libsource (lib "eagle-import") (part "CHERRY"))
    )
    (comp (ref "U$58")
      (value "CHERRY")
      (footprint "eagle-import:CHERRY")
      (libsource (lib "eagle-import") (part "CHERRY"))
    )
    (comp (ref "U$59")
      (value "CHERRY")
      (footprint "eagle-import:CHERRY")
      (libsource (lib "eagle-import") (part "CHERRY"))
    )
    (comp (ref "U$60")
      (value "CHERRY")
      (footprint "eagle-import:CHERRY")
      (libsource (lib "eagle-import") (part "CHERRY"))
    )
    (comp (ref "U$61")
      (value "CHERRY")
      (footprint "eagle-import:CHERRY")
      (libsource (lib "eagle-import") (part "CHERRY"))
    )
    (comp (ref "U$62")
      (value "SMD-BUTTON")
      (footprint "eagle-import:SMD-BUTTON")
      (libsource (lib "eagle-import") (part "SMD-BUTTON"))
    )
    (comp (ref "U$63")
      (value "TP4056SOI8")
      (footprint "eagle-import:SOIC8")
      (libsource (lib "eagle-import") (part "TP4056SOI8"))
    )
    (comp (ref "U$64")
      (value "2.5MM_ELONGATED")
      (footprint "eagle-import:2.5MM_ELONGATED")
      (libsource (lib "eagle-import") (part "2.5MM_ELONGATED"))
    )
    (comp (ref "U$65")
      (value "2.5MM_ELONGATED")
      (footprint "eagle-import:2.5MM_ELONGATED")
      (libsource (lib "eagle-import") (part "2.5MM_ELONGATED"))
    )
    (comp (ref "U$66")
      (value "2.5MM_HOLE")
      (footprint "eagle-import:2.5MM_HOLE")
      (libsource (lib "eagle-import") (part "2.5MM_HOLE"))
    )
    (comp (ref "U$67")
      (value "2.5MM_ELONGATED")
      (footprint "eagle-import:2.5MM_ELONGATED")
      (libsource (lib "eagle-import") (part "2.5MM_ELONGATED"))
    )
    (comp (ref "U$68")
      (value "STAB-2U")
      (footprint "eagle-import:STAB-2U")
      (libsource (lib "eagle-import") (part "STAB-2U"))
    )
    (comp (ref "U$69")
      (value "STAB-2U")
      (footprint "eagle-import:STAB-2U")
      (libsource (lib "eagle-import") (part "STAB-2U"))
    )
    (comp (ref "U$70")
      (value "STAB-2U")
      (footprint "eagle-import:STAB-2U")
      (libsource (lib "eagle-import") (part "STAB-2U"))
    )
    (comp (ref "U$71")
      (value "STAB-2U")
      (footprint "eagle-import:STAB-2U")
      (libsource (lib "eagle-import") (part "STAB-2U"))
    )
    (comp (ref "U$72")
      (value "STAB-6U")
      (footprint "eagle-import:STAB-6.25U")
      (libsource (lib "eagle-import") (part "STAB-6U"))
    )
    (comp (ref "U$73")
      (value "CHERRY-SOLDER")
      (footprint "eagle-import:CHERRY-SOLDER")
      (libsource (lib "eagle-import") (part "CHERRY-SOLDER"))
    )
    (comp (ref "U$74")
      (value "CHERRY-SOLDER")
      (footprint "eagle-import:CHERRY-SOLDER")
      (libsource (lib "eagle-import") (part "CHERRY-SOLDER"))
    )
    (comp (ref "U2")
      (value "AP2112K-3.3TRG1")
      (footprint "eagle-import:SOT95P285X140-5N")
      (fields (field (name "MF") "Diodes Inc."))
      (libsource (lib "eagle-import") (part "AP2112K-3.3TRG1"))
    )
  )
  (nets
    (net (code "1") (name "/BLED") (class "Default")
      (node (ref "IC3") (pin "P0.15") (pinfunction "P0.15_P0.15") (pintype "bidirectional"))
      (node (ref "LED1") (pin "A") (pinfunction "A_A") (pintype "passive"))
    )
    (net (code "2") (name "/BVOLT") (class "Default")
      (node (ref "IC3") (pin "P0.04") (pinfunction "P0.04_P0.04") (pintype "bidirectional"))
      (node (ref "R19") (pin "2") (pinfunction "2_2") (pintype "passive"))
      (node (ref "R20") (pin "1") (pinfunction "1_1") (pintype "passive"))
    )
    (net (code "3") (name "/COL1") (class "Default")
      (node (ref "IC3") (pin "P1.11") (pinfunction "P1.11_P1.11") (pintype "bidirectional"))
      (node (ref "U$1") (pin "2") (pinfunction "1_2") (pintype "bidirectional"))
      (node (ref "U$15") (pin "2") (pinfunction "1_2") (pintype "bidirectional"))
      (node (ref "U$29") (pin "2") (pinfunction "1_2") (pintype "bidirectional"))
      (node (ref "U$42") (pin "2") (pinfunction "1_2") (pintype "bidirectional"))
      (node (ref "U$54") (pin "2") (pinfunction "1_2") (pintype "bidirectional"))
    )
    (net (code "4") (name "/COL2") (class "Default")
      (node (ref "IC3") (pin "P1.10") (pinfunction "P1.10_P1.10") (pintype "bidirectional"))
      (node (ref "U$16") (pin "2") (pinfunction "1_2") (pintype "bidirectional"))
      (node (ref "U$2") (pin "2") (pinfunction "1_2") (pintype "bidirectional"))
      (node (ref "U$30") (pin "2") (pinfunction "1_2") (pintype "bidirectional"))
      (node (ref "U$43") (pin "2") (pinfunction "1_2") (pintype "bidirectional"))
      (node (ref "U$55") (pin "2") (pinfunction "1_2") (pintype "bidirectional"))
    )
    (net (code "5") (name "/COL3") (class "Default")
      (node (ref "IC3") (pin "P1.13") (pinfunction "P1.13_P1.13") (pintype "bidirectional"))
      (node (ref "U$17") (pin "2") (pinfunction "1_2") (pintype "bidirectional"))
      (node (ref "U$3") (pin "2") (pinfunction "1_2") (pintype "bidirectional"))
      (node (ref "U$31") (pin "2") (pinfunction "1_2") (pintype "bidirectional"))
      (node (ref "U$44") (pin "2") (pinfunction "1_2") (pintype "bidirectional"))
      (node (ref "U$56") (pin "2") (pinfunction "1_2") (pintype "bidirectional"))
    )
    (net (code "6") (name "/COL4") (class "Default")
      (node (ref "IC3") (pin "P1.15") (pinfunction "P1.15_P1.15") (pintype "bidirectional"))
      (node (ref "U$18") (pin "2") (pinfunction "1_2") (pintype "bidirectional"))
      (node (ref "U$32") (pin "2") (pinfunction "1_2") (pintype "bidirectional"))
      (node (ref "U$4") (pin "2") (pinfunction "1_2") (pintype "bidirectional"))
      (node (ref "U$45") (pin "2") (pinfunction "1_2") (pintype "bidirectional"))
    )
    (net (code "7") (name "/COL5") (class "Default")
      (node (ref "IC3") (pin "P0.03") (pinfunction "P0.03_P0.03") (pintype "bidirectional"))
      (node (ref "U$19") (pin "2") (pinfunction "1_2") (pintype "bidirectional"))
      (node (ref "U$33") (pin "2") (pinfunction "1_2") (pintype "bidirectional"))
      (node (ref "U$46") (pin "2") (pinfunction "1_2") (pintype "bidirectional"))
      (node (ref "U$5") (pin "2") (pinfunction "1_2") (pintype "bidirectional"))
    )
    (net (code "8") (name "/COL6") (class "Default")
      (node (ref "IC3") (pin "P0.02") (pinfunction "P0.02_P0.02") (pintype "bidirectional"))
      (node (ref "U$20") (pin "2") (pinfunction "1_2") (pintype "bidirectional"))
      (node (ref "U$34") (pin "2") (pinfunction "1_2") (pintype "bidirectional"))
      (node (ref "U$47") (pin "2") (pinfunction "1_2") (pintype "bidirectional"))
      (node (ref "U$57") (pin "2") (pinfunction "1_2") (pintype "bidirectional"))
      (node (ref "U$6") (pin "2") (pinfunction "1_2") (pintype "bidirectional"))
    )
    (net (code "9") (name "/COL7") (class "Default")
      (node (ref "IC3") (pin "P0.28") (pinfunction "P0.28_P0.28") (pintype "bidirectional"))
      (node (ref "U$21") (pin "2") (pinfunction "1_2") (pintype "bidirectional"))
      (node (ref "U$35") (pin "2") (pinfunction "1_2") (pintype "bidirectional"))
      (node (ref "U$48") (pin "2") (pinfunction "1_2") (pintype "bidirectional"))
      (node (ref "U$7") (pin "2") (pinfunction "1_2") (pintype "bidirectional"))
    )
    (net (code "10") (name "/COL8") (class "Default")
      (node (ref "IC3") (pin "P0.29") (pinfunction "P0.29_P0.29") (pintype "bidirectional"))
      (node (ref "U$22") (pin "2") (pinfunction "1_2") (pintype "bidirectional"))
      (node (ref "U$36") (pin "2") (pinfunction "1_2") (pintype "bidirectional"))
      (node (ref "U$49") (pin "2") (pinfunction "1_2") (pintype "bidirectional"))
      (node (ref "U$8") (pin "2") (pinfunction "1_2") (pintype "bidirectional"))
    )
    (net (code "11") (name "/COL9") (class "Default")
      (node (ref "IC3") (pin "P0.30") (pinfunction "P0.30_P0.30") (pintype "bidirectional"))
      (node (ref "U$23") (pin "2") (pinfunction "1_2") (pintype "bidirectional"))
      (node (ref "U$37") (pin "2") (pinfunction "1_2") (pintype "bidirectional"))
      (node (ref "U$50") (pin "2") (pinfunction "1_2") (pintype "bidirectional"))
      (node (ref "U$58") (pin "2") (pinfunction "1_2") (pintype "bidirectional"))
      (node (ref "U$9") (pin "2") (pinfunction "1_2") (pintype "bidirectional"))
    )
    (net (code "12") (name "/COL10") (class "Default")
      (node (ref "IC3") (pin "P0.31") (pinfunction "P0.31_P0.31") (pintype "bidirectional"))
      (node (ref "U$10") (pin "2") (pinfunction "1_2") (pintype "bidirectional"))
      (node (ref "U$24") (pin "2") (pinfunction "1_2") (pintype "bidirectional"))
      (node (ref "U$38") (pin "2") (pinfunction "1_2") (pintype "bidirectional"))
      (node (ref "U$51") (pin "2") (pinfunction "1_2") (pintype "bidirectional"))
      (node (ref "U$59") (pin "2") (pinfunction "1_2") (pintype "bidirectional"))
    )
    (net (code "13") (name "/COL11") (class "Default")
      (node (ref "IC3") (pin "P0.05") (pinfunction "P0.05_P0.05") (pintype "bidirectional"))
      (node (ref "U$11") (pin "2") (pinfunction "1_2") (pintype "bidirectional"))
      (node (ref "U$25") (pin "2") (pinfunction "1_2") (pintype "bidirectional"))
      (node (ref "U$39") (pin "2") (pinfunction "1_2") (pintype "bidirectional"))
      (node (ref "U$52") (pin "2") (pinfunction "1_2") (pintype "bidirectional"))
      (node (ref "U$60") (pin "2") (pinfunction "1_2") (pintype "bidirectional"))
    )
    (net (code "14") (name "/COL12") (class "Default")
      (node (ref "IC3") (pin "P0.07") (pinfunction "P0.07_P0.07") (pintype "bidirectional"))
      (node (ref "U$12") (pin "2") (pinfunction "1_2") (pintype "bidirectional"))
      (node (ref "U$26") (pin "2") (pinfunction "1_2") (pintype "bidirectional"))
      (node (ref "U$40") (pin "2") (pinfunction "1_2") (pintype "bidirectional"))
      (node (ref "U$53") (pin "2") (pinfunction "1_2") (pintype "bidirectional"))
      (node (ref "U$61") (pin "2") (pinfunction "1_2") (pintype "bidirectional"))
    )
    (net (code "15") (name "/COL13") (class "Default")
      (node (ref "IC3") (pin "P1.09") (pinfunction "P1.09_P1.09") (pintype "bidirectional"))
      (node (ref "U$13") (pin "2") (pinfunction "1_2") (pintype "bidirectional"))
      (node (ref "U$27") (pin "2") (pinfunction "1_2") (pintype "bidirectional"))
      (node (ref "U$41") (pin "2") (pinfunction "1_2") (pintype "bidirectional"))
    )
    (net (code "16") (name "/COL14") (class "Default")
      (node (ref "IC3") (pin "P0.12") (pinfunction "P0.12_P0.12") (pintype "bidirectional"))
      (node (ref "U$14") (pin "2") (pinfunction "1_2") (pintype "bidirectional"))
      (node (ref "U$28") (pin "2") (pinfunction "1_2") (pintype "bidirectional"))
      (node (ref "U$73") (pin "P$2") (pinfunction "1_P$2") (pintype "bidirectional"))
      (node (ref "U$74") (pin "P$2") (pinfunction "1_P$2") (pintype "bidirectional"))
    )
    (net (code "17") (name "/D+") (class "Default")
      (node (ref "D64") (pin "A") (pinfunction "A_A") (pintype "passive"))
      (node (ref "IC3") (pin "D+") (pinfunction "D+_D+") (pintype "bidirectional"))
      (node (ref "J2") (pin "3") (pinfunction "3_3") (pintype "passive"))
      (node (ref "J3") (pin "A6") (pinfunction "D+_A6") (pintype "bidirectional"))
      (node (ref "J3") (pin "B6") (pinfunction "D+_B6") (pintype "bidirectional"))
    )
    (net (code "18") (name "/D-") (class "Default")
      (node (ref "D65") (pin "A") (pinfunction "A_A") (pintype "passive"))
      (node (ref "IC3") (pin "D-") (pinfunction "D-_D-") (pintype "bidirectional"))
      (node (ref "J2") (pin "2") (pinfunction "2_2") (pintype "passive"))
      (node (ref "J3") (pin "A7") (pinfunction "D-_A7") (pintype "bidirectional"))
      (node (ref "J3") (pin "B7") (pinfunction "D-_B7") (pintype "bidirectional"))
    )
    (net (code "19") (name "/G_BAT") (class "Default")
      (node (ref "C5") (pin "2") (pinfunction "2_2") (pintype "passive"))
      (node (ref "CN2") (pin "1") (pinfunction "1_1") (pintype "passive"))
      (node (ref "IC1") (pin "3") (pinfunction "GND_3") (pintype "bidirectional"))
      (node (ref "J4") (pin "2") (pinfunction "2_2") (pintype "passive"))
    )
    (net (code "20") (name "/POWER_PIN") (class "Default")
      (node (ref "IC3") (pin "P0.13") (pinfunction "P0.13_P0.13") (pintype "bidirectional"))
    )
    (net (code "21") (name "/RESET") (class "Default")
      (node (ref "IC3") (pin "P0.14") (pinfunction "P0.14_P0.14") (pintype "bidirectional"))
      (node (ref "IC3") (pin "P0.16") (pinfunction "P0.16_P0.16") (pintype "bidirectional"))
      (node (ref "IC3") (pin "P0.18") (pinfunction "P0.18_P0.18") (pintype "bidirectional"))
      (node (ref "PROG1") (pin "3") (pinfunction "3_3") (pintype "passive"))
      (node (ref "R2") (pin "2") (pinfunction "2_2") (pintype "passive"))
      (node (ref "U$62") (pin "C") (pinfunction "C_C") (pintype "bidirectional"))
      (node (ref "U$62") (pin "D") (pinfunction "D_D") (pintype "bidirectional"))
    )
    (net (code "22") (name "/ROW1") (class "Default")
      (node (ref "D1") (pin "C") (pinfunction "C_C") (pintype "passive"))
      (node (ref "D10") (pin "C") (pinfunction "C_C") (pintype "passive"))
      (node (ref "D11") (pin "C") (pinfunction "C_C") (pintype "passive"))
      (node (ref "D12") (pin "C") (pinfunction "C_C") (pintype "passive"))
      (node (ref "D13") (pin "C") (pinfunction "C_C") (pintype "passive"))
      (node (ref "D14") (pin "C") (pinfunction "C_C") (pintype "passive"))
      (node (ref "D2") (pin "C") (pinfunction "C_C") (pintype "passive"))
      (node (ref "D3") (pin "C") (pinfunction "C_C") (pintype "passive"))
      (node (ref "D4") (pin "C") (pinfunction "C_C") (pintype "passive"))
      (node (ref "D5") (pin "C") (pinfunction "C_C") (pintype "passive"))
      (node (ref "D6") (pin "C") (pinfunction "C_C") (pintype "passive"))
      (node (ref "D7") (pin "C") (pinfunction "C_C") (pintype "passive"))
      (node (ref "D8") (pin "C") (pinfunction "C_C") (pintype "passive"))
      (node (ref "D9") (pin "C") (pinfunction "C_C") (pintype "passive"))
      (node (ref "IC3") (pin "P1.00") (pinfunction "P1.00_P1.00") (pintype "bidirectional"))
    )
    (net (code "23") (name "/ROW2") (class "Default")
      (node (ref "D15") (pin "C") (pinfunction "C_C") (pintype "passive"))
      (node (ref "D16") (pin "C") (pinfunction "C_C") (pintype "passive"))
      (node (ref "D17") (pin "C") (pinfunction "C_C") (pintype "passive"))
      (node (ref "D18") (pin "C") (pinfunction "C_C") (pintype "passive"))
      (node (ref "D19") (pin "C") (pinfunction "C_C") (pintype "passive"))
      (node (ref "D20") (pin "C") (pinfunction "C_C") (pintype "passive"))
      (node (ref "D21") (pin "C") (pinfunction "C_C") (pintype "passive"))
      (node (ref "D22") (pin "C") (pinfunction "C_C") (pintype "passive"))
      (node (ref "D23") (pin "C") (pinfunction "C_C") (pintype "passive"))
      (node (ref "D24") (pin "C") (pinfunction "C_C") (pintype "passive"))
      (node (ref "D25") (pin "C") (pinfunction "C_C") (pintype "passive"))
      (node (ref "D26") (pin "C") (pinfunction "C_C") (pintype "passive"))
      (node (ref "D27") (pin "C") (pinfunction "C_C") (pintype "passive"))
      (node (ref "D28") (pin "C") (pinfunction "C_C") (pintype "passive"))
      (node (ref "IC3") (pin "P0.22") (pinfunction "P0.22_P0.22") (pintype "bidirectional"))
    )
    (net (code "24") (name "/ROW3") (class "Default")
      (node (ref "D29") (pin "C") (pinfunction "C_C") (pintype "passive"))
      (node (ref "D30") (pin "C") (pinfunction "C_C") (pintype "passive"))
      (node (ref "D31") (pin "C") (pinfunction "C_C") (pintype "passive"))
      (node (ref "D32") (pin "C") (pinfunction "C_C") (pintype "passive"))
      (node (ref "D33") (pin "C") (pinfunction "C_C") (pintype "passive"))
      (node (ref "D34") (pin "C") (pinfunction "C_C") (pintype "passive"))
      (node (ref "D35") (pin "C") (pinfunction "C_C") (pintype "passive"))
      (node (ref "D36") (pin "C") (pinfunction "C_C") (pintype "passive"))
      (node (ref "D37") (pin "C") (pinfunction "C_C") (pintype "passive"))
      (node (ref "D38") (pin "C") (pinfunction "C_C") (pintype "passive"))
      (node (ref "D39") (pin "C") (pinfunction "C_C") (pintype "passive"))
      (node (ref "D40") (pin "C") (pinfunction "C_C") (pintype "passive"))
      (node (ref "D41") (pin "C") (pinfunction "C_C") (pintype "passive"))
      (node (ref "D62") (pin "C") (pinfunction "C_C") (pintype "passive"))
      (node (ref "IC3") (pin "P0.19") (pinfunction "P0.19_P0.19") (pintype "bidirectional"))
    )
    (net (code "25") (name "/ROW4") (class "Default")
      (node (ref "D42") (pin "C") (pinfunction "C_C") (pintype "passive"))
      (node (ref "D43") (pin "C") (pinfunction "C_C") (pintype "passive"))
      (node (ref "D44") (pin "C") (pinfunction "C_C") (pintype "passive"))
      (node (ref "D45") (pin "C") (pinfunction "C_C") (pintype "passive"))
      (node (ref "D46") (pin "C") (pinfunction "C_C") (pintype "passive"))
      (node (ref "D47") (pin "C") (pinfunction "C_C") (pintype "passive"))
      (node (ref "D48") (pin "C") (pinfunction "C_C") (pintype "passive"))
      (node (ref "D49") (pin "C") (pinfunction "C_C") (pintype "passive"))
      (node (ref "D50") (pin "C") (pinfunction "C_C") (pintype "passive"))
      (node (ref "D51") (pin "C") (pinfunction "C_C") (pintype "passive"))
      (node (ref "D52") (pin "C") (pinfunction "C_C") (pintype "passive"))
      (node (ref "D53") (pin "C") (pinfunction "C_C") (pintype "passive"))
      (node (ref "IC3") (pin "P0.21") (pinfunction "P0.21_P0.21") (pintype "bidirectional"))
    )
    (net (code "26") (name "/ROW5") (class "Default")
      (node (ref "D54") (pin "C") (pinfunction "C_C") (pintype "passive"))
      (node (ref "D55") (pin "C") (pinfunction "C_C") (pintype "passive"))
      (node (ref "D56") (pin "C") (pinfunction "C_C") (pintype "passive"))
      (node (ref "D57") (pin "C") (pinfunction "C_C") (pintype "passive"))
      (node (ref "D58") (pin "C") (pinfunction "C_C") (pintype "passive"))
      (node (ref "D59") (pin "C") (pinfunction "C_C") (pintype "passive"))
      (node (ref "D60") (pin "C") (pinfunction "C_C") (pintype "passive"))
      (node (ref "D61") (pin "C") (pinfunction "C_C") (pintype "passive"))
      (node (ref "IC3") (pin "P0.23") (pinfunction "P0.23_P0.23") (pintype "bidirectional"))
    )
    (net (code "27") (name "/RXD") (class "Default")
      (node (ref "IC3") (pin "P0.08") (pinfunction "P0.08_P0.08") (pintype "bidirectional"))
    )
    (net (code "28") (name "/SCK") (class "Default")
      (node (ref "IC3") (pin "SWDCLK") (pinfunction "SWDCLK_SWDCLK") (pintype "bidirectional"))
      (node (ref "PROG1") (pin "4") (pinfunction "4_4") (pintype "passive"))
    )
    (net (code "29") (name "/SWD") (class "Default")
      (node (ref "IC3") (pin "SWDIO") (pinfunction "SWDIO_SWDIO") (pintype "bidirectional"))
      (node (ref "PROG1") (pin "5") (pinfunction "5_5") (pintype "passive"))
    )
    (net (code "30") (name "/TXD") (class "Default")
      (node (ref "IC3") (pin "P0.06") (pinfunction "P0.06_P0.06") (pintype "bidirectional"))
    )
    (net (code "31") (name "/VDD_NRF") (class "Default")
      (node (ref "D66") (pin "A") (pinfunction "A_A") (pintype "passive"))
      (node (ref "IC3") (pin "VDD_NRF") (pinfunction "VDD_NRF_VDD_NRF") (pintype "bidirectional"))
      (node (ref "PROG1") (pin "1") (pinfunction "1_1") (pintype "passive"))
      (node (ref "R2") (pin "1") (pinfunction "1_1") (pintype "passive"))
      (node (ref "U2") (pin "5") (pinfunction "VOUT_5") (pintype "power_in"))
    )
    (net (code "32") (name "GND") (class "Default")
      (node (ref "C4") (pin "2") (pinfunction "2_2") (pintype "passive"))
      (node (ref "C6") (pin "2") (pinfunction "2_2") (pintype "passive"))
      (node (ref "D64") (pin "C") (pinfunction "C_C") (pintype "passive"))
      (node (ref "D65") (pin "C") (pinfunction "C_C") (pintype "passive"))
      (node (ref "D66") (pin "C") (pinfunction "C_C") (pintype "passive"))
      (node (ref "D67") (pin "C") (pinfunction "C_C") (pintype "passive"))
      (node (ref "IC1") (pin "1") (pinfunction "VM_1") (pintype "bidirectional"))
      (node (ref "IC3") (pin "GND") (pinfunction "GND1_GND") (pintype "bidirectional"))
      (node (ref "IC3") (pin "GND1") (pinfunction "GND2_GND1") (pintype "bidirectional"))
      (node (ref "IC3") (pin "GND2") (pinfunction "GND3_GND2") (pintype "bidirectional"))
      (node (ref "J2") (pin "4") (pinfunction "4_4") (pintype "passive"))
      (node (ref "J3") (pin "GND") (pinfunction "GND_GND") (pintype "bidirectional"))
      (node (ref "J3") (pin "GND2") (pinfunction "GND_GND2") (pintype "bidirectional"))
      (node (ref "J3") (pin "SHLD1") (pinfunction "SHLD_SHLD1") (pintype "bidirectional"))
      (node (ref "J3") (pin "SHLD2") (pinfunction "SHLD_SHLD2") (pintype "bidirectional"))
      (node (ref "J3") (pin "SHLD3") (pinfunction "SHLD_SHLD3") (pintype "bidirectional"))
      (node (ref "J3") (pin "SHLD4") (pinfunction "SHLD_SHLD4") (pintype "bidirectional"))
      (node (ref "J3") (pin "SHLD5") (pinfunction "SHLD_SHLD5") (pintype "bidirectional"))
      (node (ref "J3") (pin "SHLD6") (pinfunction "SHLD_SHLD6") (pintype "bidirectional"))
      (node (ref "J3") (pin "SHLD7") (pinfunction "SHLD_SHLD7") (pintype "bidirectional"))
      (node (ref "J3") (pin "SHLD8") (pinfunction "SHLD_SHLD8") (pintype "bidirectional"))
      (node (ref "PROG1") (pin "2") (pinfunction "2_2") (pintype "passive"))
      (node (ref "R1") (pin "1") (pinfunction "1_1") (pintype "passive"))
      (node (ref "R11") (pin "1") (pinfunction "1_1") (pintype "passive"))
      (node (ref "R12") (pin "1") (pinfunction "1_1") (pintype "passive"))
      (node (ref "R13") (pin "1") (pinfunction "1_1") (pintype "passive"))
      (node (ref "R17") (pin "1") (pinfunction "1_1") (pintype "passive"))
      (node (ref "R20") (pin "2") (pinfunction "2_2") (pintype "passive"))
      (node (ref "U$62") (pin "A") (pinfunction "A_A") (pintype "bidirectional"))
      (node (ref "U$62") (pin "B") (pinfunction "B_B") (pintype "bidirectional"))
      (node (ref "U$63") (pin "1") (pinfunction "TEMP_1") (pintype "bidirectional"))
      (node (ref "U$63") (pin "3") (pinfunction "GND_3") (pintype "bidirectional"))
      (node (ref "U$64") (pin "P$1") (pinfunction "P$1_P$1") (pintype "bidirectional"))
      (node (ref "U$64") (pin "P$2") (pinfunction "P$1_P$2") (pintype "bidirectional"))
      (node (ref "U$65") (pin "P$1") (pinfunction "P$1_P$1") (pintype "bidirectional"))
      (node (ref "U$65") (pin "P$2") (pinfunction "P$1_P$2") (pintype "bidirectional"))
      (node (ref "U$66") (pin "P$1") (pinfunction "P$1_P$1") (pintype "bidirectional"))
      (node (ref "U$66") (pin "P$2") (pinfunction "P$1_P$2") (pintype "bidirectional"))
      (node (ref "U$67") (pin "P$1") (pinfunction "P$1_P$1") (pintype "bidirectional"))
      (node (ref "U$67") (pin "P$2") (pinfunction "P$1_P$2") (pintype "bidirectional"))
      (node (ref "U2") (pin "2") (pinfunction "GND_2") (pintype "power_in"))
    )
    (net (code "33") (name "Net-(D63-K)") (class "Default")
      (node (ref "C6") (pin "1") (pinfunction "1_1") (pintype "passive"))
      (node (ref "D63") (pin "1") (pinfunction "K_1") (pintype "bidirectional"))
      (node (ref "Q5") (pin "2") (pinfunction "S_2") (pintype "passive"))
      (node (ref "U2") (pin "1") (pinfunction "VIN_1") (pintype "power_in"))
      (node (ref "U2") (pin "3") (pinfunction "EN_3") (pintype "input"))
    )
    (net (code "34") (name "Net-(FUSE-Pad2)") (class "Default")
      (node (ref "FUSE") (pin "2") (pinfunction "2_2") (pintype "passive"))
      (node (ref "J3") (pin "VBUS1") (pinfunction "VBUS_VBUS1") (pintype "bidirectional"))
      (node (ref "J3") (pin "VBUS2") (pinfunction "VBUS_VBUS2") (pintype "bidirectional"))
    )
    (net (code "35") (name "Net-(IC1-VDD)") (class "Default")
      (node (ref "C5") (pin "1") (pinfunction "1_1") (pintype "passive"))
      (node (ref "IC1") (pin "2") (pinfunction "VDD_2") (pintype "bidirectional"))
      (node (ref "R15") (pin "1") (pinfunction "1_1") (pintype "passive"))
    )
    (net (code "36") (name "Net-(IC3-PadP0.17)") (class "Default")
      (node (ref "IC3") (pin "P0.17") (pinfunction "P0.17_P0.17") (pintype "bidirectional"))
      (node (ref "J1") (pin "5") (pinfunction "5_5") (pintype "passive"))
    )
    (net (code "37") (name "Net-(IC3-PadP0.20)") (class "Default")
      (node (ref "IC3") (pin "P0.20") (pinfunction "P0.20_P0.20") (pintype "bidirectional"))
      (node (ref "J1") (pin "4") (pinfunction "4_4") (pintype "passive"))
    )
    (net (code "38") (name "Net-(IC3-PadP0.24)") (class "Default")
      (node (ref "IC3") (pin "P0.24") (pinfunction "P0.24_P0.24") (pintype "bidirectional"))
      (node (ref "J1") (pin "3") (pinfunction "3_3") (pintype "passive"))
    )
    (net (code "39") (name "Net-(IC3-PadP1.05)") (class "Default")
      (node (ref "IC3") (pin "P1.05") (pinfunction "P1.05_P1.05") (pintype "bidirectional"))
      (node (ref "J1") (pin "2") (pinfunction "2_2") (pintype "passive"))
    )
    (net (code "40") (name "Net-(IC3-PadP1.07)") (class "Default")
      (node (ref "IC3") (pin "P1.07") (pinfunction "P1.07_P1.07") (pintype "bidirectional"))
      (node (ref "J1") (pin "1") (pinfunction "1_1") (pintype "passive"))
    )
    (net (code "41") (name "Net-(J3-CC1)") (class "Default")
      (node (ref "J3") (pin "A5") (pinfunction "CC1_A5") (pintype "bidirectional"))
      (node (ref "R12") (pin "2") (pinfunction "2_2") (pintype "passive"))
    )
    (net (code "42") (name "Net-(J3-CC2)") (class "Default")
      (node (ref "J3") (pin "B5") (pinfunction "CC2_B5") (pintype "bidirectional"))
      (node (ref "R11") (pin "2") (pinfunction "2_2") (pintype "passive"))
    )
    (net (code "43") (name "Net-(LED1-PadC)") (class "Default")
      (node (ref "LED1") (pin "C") (pinfunction "C_C") (pintype "passive"))
      (node (ref "R1") (pin "2") (pinfunction "2_2") (pintype "passive"))
    )
    (net (code "44") (name "Net-(LED2-PadC)") (class "Default")
      (node (ref "LED2") (pin "C") (pinfunction "C_C") (pintype "passive"))
      (node (ref "R14") (pin "1") (pinfunction "1_1") (pintype "passive"))
    )
    (net (code "45") (name "Net-(U$1-2)") (class "Default")
      (node (ref "D1") (pin "A") (pinfunction "A_A") (pintype "passive"))
      (node (ref "U$1") (pin "1") (pinfunction "2_1") (pintype "bidirectional"))
    )
    (net (code "46") (name "Net-(U$2-2)") (class "Default")
      (node (ref "D2") (pin "A") (pinfunction "A_A") (pintype "passive"))
      (node (ref "U$2") (pin "1") (pinfunction "2_1") (pintype "bidirectional"))
    )
    (net (code "47") (name "Net-(U$3-2)") (class "Default")
      (node (ref "D3") (pin "A") (pinfunction "A_A") (pintype "passive"))
      (node (ref "U$3") (pin "1") (pinfunction "2_1") (pintype "bidirectional"))
    )
    (net (code "48") (name "Net-(U$4-2)") (class "Default")
      (node (ref "D4") (pin "A") (pinfunction "A_A") (pintype "passive"))
      (node (ref "U$4") (pin "1") (pinfunction "2_1") (pintype "bidirectional"))
    )
    (net (code "49") (name "Net-(U$5-2)") (class "Default")
      (node (ref "D5") (pin "A") (pinfunction "A_A") (pintype "passive"))
      (node (ref "U$5") (pin "1") (pinfunction "2_1") (pintype "bidirectional"))
    )
    (net (code "50") (name "Net-(U$6-2)") (class "Default")
      (node (ref "D6") (pin "A") (pinfunction "A_A") (pintype "passive"))
      (node (ref "U$6") (pin "1") (pinfunction "2_1") (pintype "bidirectional"))
    )
    (net (code "51") (name "Net-(U$7-2)") (class "Default")
      (node (ref "D7") (pin "A") (pinfunction "A_A") (pintype "passive"))
      (node (ref "U$7") (pin "1") (pinfunction "2_1") (pintype "bidirectional"))
    )
    (net (code "52") (name "Net-(U$8-2)") (class "Default")
      (node (ref "D8") (pin "A") (pinfunction "A_A") (pintype "passive"))
      (node (ref "U$8") (pin "1") (pinfunction "2_1") (pintype "bidirectional"))
    )
    (net (code "53") (name "Net-(U$9-2)") (class "Default")
      (node (ref "D9") (pin "A") (pinfunction "A_A") (pintype "passive"))
      (node (ref "U$9") (pin "1") (pinfunction "2_1") (pintype "bidirectional"))
    )
    (net (code "54") (name "Net-(U$10-2)") (class "Default")
      (node (ref "D10") (pin "A") (pinfunction "A_A") (pintype "passive"))
      (node (ref "U$10") (pin "1") (pinfunction "2_1") (pintype "bidirectional"))
    )
    (net (code "55") (name "Net-(U$11-2)") (class "Default")
      (node (ref "D11") (pin "A") (pinfunction "A_A") (pintype "passive"))
      (node (ref "U$11") (pin "1") (pinfunction "2_1") (pintype "bidirectional"))
    )
    (net (code "56") (name "Net-(U$12-2)") (class "Default")
      (node (ref "D12") (pin "A") (pinfunction "A_A") (pintype "passive"))
      (node (ref "U$12") (pin "1") (pinfunction "2_1") (pintype "bidirectional"))
    )
    (net (code "57") (name "Net-(U$13-2)") (class "Default")
      (node (ref "D13") (pin "A") (pinfunction "A_A") (pintype "passive"))
      (node (ref "U$13") (pin "1") (pinfunction "2_1") (pintype "bidirectional"))
    )
    (net (code "58") (name "Net-(U$14-2)") (class "Default")
      (node (ref "D14") (pin "A") (pinfunction "A_A") (pintype "passive"))
      (node (ref "U$14") (pin "1") (pinfunction "2_1") (pintype "bidirectional"))
      (node (ref "U$73") (pin "P$1") (pinfunction "2_P$1") (pintype "bidirectional"))
    )
    (net (code "59") (name "Net-(U$15-2)") (class "Default")
      (node (ref "D15") (pin "A") (pinfunction "A_A") (pintype "passive"))
      (node (ref "U$15") (pin "1") (pinfunction "2_1") (pintype "bidirectional"))
    )
    (net (code "60") (name "Net-(U$16-2)") (class "Default")
      (node (ref "D16") (pin "A") (pinfunction "A_A") (pintype "passive"))
      (node (ref "U$16") (pin "1") (pinfunction "2_1") (pintype "bidirectional"))
    )
    (net (code "61") (name "Net-(U$17-2)") (class "Default")
      (node (ref "D17") (pin "A") (pinfunction "A_A") (pintype "passive"))
      (node (ref "U$17") (pin "1") (pinfunction "2_1") (pintype "bidirectional"))
    )
    (net (code "62") (name "Net-(U$18-2)") (class "Default")
      (node (ref "D18") (pin "A") (pinfunction "A_A") (pintype "passive"))
      (node (ref "U$18") (pin "1") (pinfunction "2_1") (pintype "bidirectional"))
    )
    (net (code "63") (name "Net-(U$19-2)") (class "Default")
      (node (ref "D19") (pin "A") (pinfunction "A_A") (pintype "passive"))
      (node (ref "U$19") (pin "1") (pinfunction "2_1") (pintype "bidirectional"))
    )
    (net (code "64") (name "Net-(U$20-2)") (class "Default")
      (node (ref "D20") (pin "A") (pinfunction "A_A") (pintype "passive"))
      (node (ref "U$20") (pin "1") (pinfunction "2_1") (pintype "bidirectional"))
    )
    (net (code "65") (name "Net-(U$21-2)") (class "Default")
      (node (ref "D21") (pin "A") (pinfunction "A_A") (pintype "passive"))
      (node (ref "U$21") (pin "1") (pinfunction "2_1") (pintype "bidirectional"))
    )
    (net (code "66") (name "Net-(U$22-2)") (class "Default")
      (node (ref "D22") (pin "A") (pinfunction "A_A") (pintype "passive"))
      (node (ref "U$22") (pin "1") (pinfunction "2_1") (pintype "bidirectional"))
    )
    (net (code "67") (name "Net-(U$23-2)") (class "Default")
      (node (ref "D23") (pin "A") (pinfunction "A_A") (pintype "passive"))
      (node (ref "U$23") (pin "1") (pinfunction "2_1") (pintype "bidirectional"))
    )
    (net (code "68") (name "Net-(U$24-2)") (class "Default")
      (node (ref "D24") (pin "A") (pinfunction "A_A") (pintype "passive"))
      (node (ref "U$24") (pin "1") (pinfunction "2_1") (pintype "bidirectional"))
    )
    (net (code "69") (name "Net-(U$25-2)") (class "Default")
      (node (ref "D25") (pin "A") (pinfunction "A_A") (pintype "passive"))
      (node (ref "U$25") (pin "1") (pinfunction "2_1") (pintype "bidirectional"))
    )
    (net (code "70") (name "Net-(U$26-2)") (class "Default")
      (node (ref "D26") (pin "A") (pinfunction "A_A") (pintype "passive"))
      (node (ref "U$26") (pin "1") (pinfunction "2_1") (pintype "bidirectional"))
    )
    (net (code "71") (name "Net-(U$27-2)") (class "Default")
      (node (ref "D27") (pin "A") (pinfunction "A_A") (pintype "passive"))
      (node (ref "U$27") (pin "1") (pinfunction "2_1") (pintype "bidirectional"))
    )
    (net (code "72") (name "Net-(U$28-2)") (class "Default")
      (node (ref "D28") (pin "A") (pinfunction "A_A") (pintype "passive"))
      (node (ref "U$28") (pin "1") (pinfunction "2_1") (pintype "bidirectional"))
    )
    (net (code "73") (name "Net-(U$29-2)") (class "Default")
      (node (ref "D29") (pin "A") (pinfunction "A_A") (pintype "passive"))
      (node (ref "U$29") (pin "1") (pinfunction "2_1") (pintype "bidirectional"))
    )
    (net (code "74") (name "Net-(U$30-2)") (class "Default")
      (node (ref "D30") (pin "A") (pinfunction "A_A") (pintype "passive"))
      (node (ref "U$30") (pin "1") (pinfunction "2_1") (pintype "bidirectional"))
    )
    (net (code "75") (name "Net-(U$31-2)") (class "Default")
      (node (ref "D31") (pin "A") (pinfunction "A_A") (pintype "passive"))
      (node (ref "U$31") (pin "1") (pinfunction "2_1") (pintype "bidirectional"))
    )
    (net (code "76") (name "Net-(U$32-2)") (class "Default")
      (node (ref "D32") (pin "A") (pinfunction "A_A") (pintype "passive"))
      (node (ref "U$32") (pin "1") (pinfunction "2_1") (pintype "bidirectional"))
    )
    (net (code "77") (name "Net-(U$33-2)") (class "Default")
      (node (ref "D33") (pin "A") (pinfunction "A_A") (pintype "passive"))
      (node (ref "U$33") (pin "1") (pinfunction "2_1") (pintype "bidirectional"))
    )
    (net (code "78") (name "Net-(U$34-2)") (class "Default")
      (node (ref "D34") (pin "A") (pinfunction "A_A") (pintype "passive"))
      (node (ref "U$34") (pin "1") (pinfunction "2_1") (pintype "bidirectional"))
    )
    (net (code "79") (name "Net-(U$35-2)") (class "Default")
      (node (ref "D35") (pin "A") (pinfunction "A_A") (pintype "passive"))
      (node (ref "U$35") (pin "1") (pinfunction "2_1") (pintype "bidirectional"))
    )
    (net (code "80") (name "Net-(U$36-2)") (class "Default")
      (node (ref "D36") (pin "A") (pinfunction "A_A") (pintype "passive"))
      (node (ref "U$36") (pin "1") (pinfunction "2_1") (pintype "bidirectional"))
    )
    (net (code "81") (name "Net-(U$37-2)") (class "Default")
      (node (ref "D37") (pin "A") (pinfunction "A_A") (pintype "passive"))
      (node (ref "U$37") (pin "1") (pinfunction "2_1") (pintype "bidirectional"))
    )
    (net (code "82") (name "Net-(U$38-2)") (class "Default")
      (node (ref "D38") (pin "A") (pinfunction "A_A") (pintype "passive"))
      (node (ref "U$38") (pin "1") (pinfunction "2_1") (pintype "bidirectional"))
    )
    (net (code "83") (name "Net-(U$39-2)") (class "Default")
      (node (ref "D39") (pin "A") (pinfunction "A_A") (pintype "passive"))
      (node (ref "U$39") (pin "1") (pinfunction "2_1") (pintype "bidirectional"))
    )
    (net (code "84") (name "Net-(U$40-2)") (class "Default")
      (node (ref "D40") (pin "A") (pinfunction "A_A") (pintype "passive"))
      (node (ref "U$40") (pin "1") (pinfunction "2_1") (pintype "bidirectional"))
    )
    (net (code "85") (name "Net-(U$41-2)") (class "Default")
      (node (ref "D41") (pin "A") (pinfunction "A_A") (pintype "passive"))
      (node (ref "U$41") (pin "1") (pinfunction "2_1") (pintype "bidirectional"))
    )
    (net (code "86") (name "Net-(U$42-2)") (class "Default")
      (node (ref "D42") (pin "A") (pinfunction "A_A") (pintype "passive"))
      (node (ref "U$42") (pin "1") (pinfunction "2_1") (pintype "bidirectional"))
    )
    (net (code "87") (name "Net-(U$43-2)") (class "Default")
      (node (ref "D43") (pin "A") (pinfunction "A_A") (pintype "passive"))
      (node (ref "U$43") (pin "1") (pinfunction "2_1") (pintype "bidirectional"))
    )
    (net (code "88") (name "Net-(U$44-2)") (class "Default")
      (node (ref "D44") (pin "A") (pinfunction "A_A") (pintype "passive"))
      (node (ref "U$44") (pin "1") (pinfunction "2_1") (pintype "bidirectional"))
    )
    (net (code "89") (name "Net-(U$45-2)") (class "Default")
      (node (ref "D45") (pin "A") (pinfunction "A_A") (pintype "passive"))
      (node (ref "U$45") (pin "1") (pinfunction "2_1") (pintype "bidirectional"))
    )
    (net (code "90") (name "Net-(U$46-2)") (class "Default")
      (node (ref "D46") (pin "A") (pinfunction "A_A") (pintype "passive"))
      (node (ref "U$46") (pin "1") (pinfunction "2_1") (pintype "bidirectional"))
    )
    (net (code "91") (name "Net-(U$47-2)") (class "Default")
      (node (ref "D47") (pin "A") (pinfunction "A_A") (pintype "passive"))
      (node (ref "U$47") (pin "1") (pinfunction "2_1") (pintype "bidirectional"))
    )
    (net (code "92") (name "Net-(U$48-2)") (class "Default")
      (node (ref "D48") (pin "A") (pinfunction "A_A") (pintype "passive"))
      (node (ref "U$48") (pin "1") (pinfunction "2_1") (pintype "bidirectional"))
    )
    (net (code "93") (name "Net-(U$49-2)") (class "Default")
      (node (ref "D49") (pin "A") (pinfunction "A_A") (pintype "passive"))
      (node (ref "U$49") (pin "1") (pinfunction "2_1") (pintype "bidirectional"))
    )
    (net (code "94") (name "Net-(U$50-2)") (class "Default")
      (node (ref "D50") (pin "A") (pinfunction "A_A") (pintype "passive"))
      (node (ref "U$50") (pin "1") (pinfunction "2_1") (pintype "bidirectional"))
    )
    (net (code "95") (name "Net-(U$51-2)") (class "Default")
      (node (ref "D51") (pin "A") (pinfunction "A_A") (pintype "passive"))
      (node (ref "U$51") (pin "1") (pinfunction "2_1") (pintype "bidirectional"))
    )
    (net (code "96") (name "Net-(U$52-2)") (class "Default")
      (node (ref "D52") (pin "A") (pinfunction "A_A") (pintype "passive"))
      (node (ref "U$52") (pin "1") (pinfunction "2_1") (pintype "bidirectional"))
    )
    (net (code "97") (name "Net-(U$53-2)") (class "Default")
      (node (ref "D53") (pin "A") (pinfunction "A_A") (pintype "passive"))
      (node (ref "U$53") (pin "1") (pinfunction "2_1") (pintype "bidirectional"))
    )
    (net (code "98") (name "Net-(U$54-2)") (class "Default")
      (node (ref "D54") (pin "A") (pinfunction "A_A") (pintype "passive"))
      (node (ref "U$54") (pin "1") (pinfunction "2_1") (pintype "bidirectional"))
    )
    (net (code "99") (name "Net-(U$55-2)") (class "Default")
      (node (ref "D55") (pin "A") (pinfunction "A_A") (pintype "passive"))
      (node (ref "U$55") (pin "1") (pinfunction "2_1") (pintype "bidirectional"))
    )
    (net (code "100") (name "Net-(U$56-2)") (class "Default")
      (node (ref "D56") (pin "A") (pinfunction "A_A") (pintype "passive"))
      (node (ref "U$56") (pin "1") (pinfunction "2_1") (pintype "bidirectional"))
    )
    (net (code "101") (name "Net-(U$57-2)") (class "Default")
      (node (ref "D57") (pin "A") (pinfunction "A_A") (pintype "passive"))
      (node (ref "U$57") (pin "1") (pinfunction "2_1") (pintype "bidirectional"))
    )
    (net (code "102") (name "Net-(U$58-2)") (class "Default")
      (node (ref "D58") (pin "A") (pinfunction "A_A") (pintype "passive"))
      (node (ref "U$58") (pin "1") (pinfunction "2_1") (pintype "bidirectional"))
    )
    (net (code "103") (name "Net-(U$59-2)") (class "Default")
      (node (ref "D59") (pin "A") (pinfunction "A_A") (pintype "passive"))
      (node (ref "U$59") (pin "1") (pinfunction "2_1") (pintype "bidirectional"))
    )
    (net (code "104") (name "Net-(U$60-2)") (class "Default")
      (node (ref "D60") (pin "A") (pinfunction "A_A") (pintype "passive"))
      (node (ref "U$60") (pin "1") (pinfunction "2_1") (pintype "bidirectional"))
    )
    (net (code "105") (name "Net-(U$61-2)") (class "Default")
      (node (ref "D61") (pin "A") (pinfunction "A_A") (pintype "passive"))
      (node (ref "U$61") (pin "1") (pinfunction "2_1") (pintype "bidirectional"))
    )
    (net (code "106") (name "Net-(U$63-PROG)") (class "Default")
      (node (ref "R13") (pin "2") (pinfunction "2_2") (pintype "passive"))
      (node (ref "U$63") (pin "2") (pinfunction "PROG_2") (pintype "bidirectional"))
    )
    (net (code "107") (name "Net-(U$63-~{CHRG})") (class "Default")
      (node (ref "R14") (pin "2") (pinfunction "2_2") (pintype "passive"))
      (node (ref "U$63") (pin "7") (pinfunction "~{CHRG}_7") (pintype "bidirectional"))
    )
    (net (code "108") (name "Net-(U$74-2)") (class "Default")
      (node (ref "D62") (pin "A") (pinfunction "A_A") (pintype "passive"))
      (node (ref "U$74") (pin "P$1") (pinfunction "2_P$1") (pintype "bidirectional"))
    )
    (net (code "109") (name "V_BATT") (class "Default")
      (node (ref "CN2") (pin "2") (pinfunction "2_2") (pintype "passive"))
      (node (ref "J4") (pin "1") (pinfunction "1_1") (pintype "passive"))
      (node (ref "Q5") (pin "3") (pinfunction "D_3") (pintype "passive"))
      (node (ref "R15") (pin "2") (pinfunction "2_2") (pintype "passive"))
      (node (ref "R19") (pin "1") (pinfunction "1_1") (pintype "passive"))
      (node (ref "U$63") (pin "5") (pinfunction "BAT_5") (pintype "bidirectional"))
    )
    (net (code "110") (name "V_USB") (class "Default")
      (node (ref "C4") (pin "1") (pinfunction "1_1") (pintype "passive"))
      (node (ref "D63") (pin "2") (pinfunction "A_2") (pintype "bidirectional"))
      (node (ref "D67") (pin "A") (pinfunction "A_A") (pintype "passive"))
      (node (ref "FUSE") (pin "1") (pinfunction "1_1") (pintype "passive"))
      (node (ref "IC3") (pin "VBUS") (pinfunction "VBUS_VBUS") (pintype "bidirectional"))
      (node (ref "J2") (pin "1") (pinfunction "1_1") (pintype "passive"))
      (node (ref "LED2") (pin "A") (pinfunction "A_A") (pintype "passive"))
      (node (ref "PROG1") (pin "6") (pinfunction "6_6") (pintype "passive"))
      (node (ref "Q5") (pin "1") (pinfunction "G_1") (pintype "passive"))
      (node (ref "R17") (pin "2") (pinfunction "2_2") (pintype "passive"))
      (node (ref "U$63") (pin "4") (pinfunction "VCC_4") (pintype "bidirectional"))
      (node (ref "U$63") (pin "8") (pinfunction "CE_8") (pintype "bidirectional"))
    )
    (net (code "111") (name "unconnected-(D68-PadA)") (class "Default")
      (node (ref "D68") (pin "A") (pinfunction "A_A") (pintype "passive"))
    )
    (net (code "112") (name "unconnected-(D68-PadC)") (class "Default")
      (node (ref "D68") (pin "C") (pinfunction "C_C") (pintype "passive"))
    )
    (net (code "113") (name "unconnected-(D69-PadA)") (class "Default")
      (node (ref "D69") (pin "A") (pinfunction "A_A") (pintype "passive"))
    )
    (net (code "114") (name "unconnected-(D69-PadC)") (class "Default")
      (node (ref "D69") (pin "C") (pinfunction "C_C") (pintype "passive"))
    )
    (net (code "115") (name "unconnected-(D70-PadA)") (class "Default")
      (node (ref "D70") (pin "A") (pinfunction "A_A") (pintype "passive"))
    )
    (net (code "116") (name "unconnected-(D70-PadC)") (class "Default")
      (node (ref "D70") (pin "C") (pinfunction "C_C") (pintype "passive"))
    )
    (net (code "117") (name "unconnected-(D71-PadA)") (class "Default")
      (node (ref "D71") (pin "A") (pinfunction "A_A") (pintype "passive"))
    )
    (net (code "118") (name "unconnected-(D71-PadC)") (class "Default")
      (node (ref "D71") (pin "C") (pinfunction "C_C") (pintype "passive"))
    )
    (net (code "119") (name "unconnected-(IC3-PadP0.09)") (class "Default")
      (node (ref "IC3") (pin "P0.09") (pinfunction "P0.09_P0.09") (pintype "bidirectional"))
    )
    (net (code "120") (name "unconnected-(IC3-PadP0.10)") (class "Default")
      (node (ref "IC3") (pin "P0.10") (pinfunction "P0.10_P0.10") (pintype "bidirectional"))
    )
    (net (code "121") (name "unconnected-(IC3-PadP0.11)") (class "Default")
      (node (ref "IC3") (pin "P0.11") (pinfunction "P0.11_P0.11") (pintype "bidirectional"))
    )
    (net (code "122") (name "unconnected-(IC3-PadP0.25)") (class "Default")
      (node (ref "IC3") (pin "P0.25") (pinfunction "P0.25_P0.25") (pintype "bidirectional"))
    )
    (net (code "123") (name "unconnected-(IC3-PadP0.26)") (class "Default")
      (node (ref "IC3") (pin "P0.26") (pinfunction "P0.26_P0.26") (pintype "bidirectional"))
    )
    (net (code "124") (name "unconnected-(IC3-PadP0.27)") (class "Default")
      (node (ref "IC3") (pin "P0.27") (pinfunction "P0.27_P0.27") (pintype "bidirectional"))
    )
    (net (code "125") (name "unconnected-(IC3-PadP1.01)") (class "Default")
      (node (ref "IC3") (pin "P1.01") (pinfunction "P1.01_P1.01") (pintype "bidirectional"))
    )
    (net (code "126") (name "unconnected-(IC3-PadP1.02)") (class "Default")
      (node (ref "IC3") (pin "P1.02") (pinfunction "P1.02_P1.02") (pintype "bidirectional"))
    )
    (net (code "127") (name "unconnected-(IC3-PadP1.03)") (class "Default")
      (node (ref "IC3") (pin "P1.03") (pinfunction "P1.03_P1.03") (pintype "bidirectional"))
    )
    (net (code "128") (name "unconnected-(IC3-PadP1.04)") (class "Default")
      (node (ref "IC3") (pin "P1.04") (pinfunction "P1.04_P1.04") (pintype "bidirectional"))
    )
    (net (code "129") (name "unconnected-(IC3-PadP1.06)") (class "Default")
      (node (ref "IC3") (pin "P1.06") (pinfunction "P1.06_P1.06") (pintype "bidirectional"))
    )
    (net (code "130") (name "unconnected-(IC3-PadP1.08)") (class "Default")
      (node (ref "IC3") (pin "P1.08") (pinfunction "P1.08_P1.08") (pintype "bidirectional"))
    )
    (net (code "131") (name "unconnected-(IC3-PadP1.12)") (class "Default")
      (node (ref "IC3") (pin "P1.12") (pinfunction "P1.12_P1.12") (pintype "bidirectional"))
    )
    (net (code "132") (name "unconnected-(IC3-PadP1.14)") (class "Default")
      (node (ref "IC3") (pin "P1.14") (pinfunction "P1.14_P1.14") (pintype "bidirectional"))
    )
    (net (code "133") (name "unconnected-(U$63-~{STDBY}-Pad6)") (class "Default")
      (node (ref "U$63") (pin "6") (pinfunction "~{STDBY}_6") (pintype "bidirectional"))
    )
  )
)
